# MAIN_BQ_INDUCTOR_REV.net
KiCad netlist of a schematic drawn in EAGLE
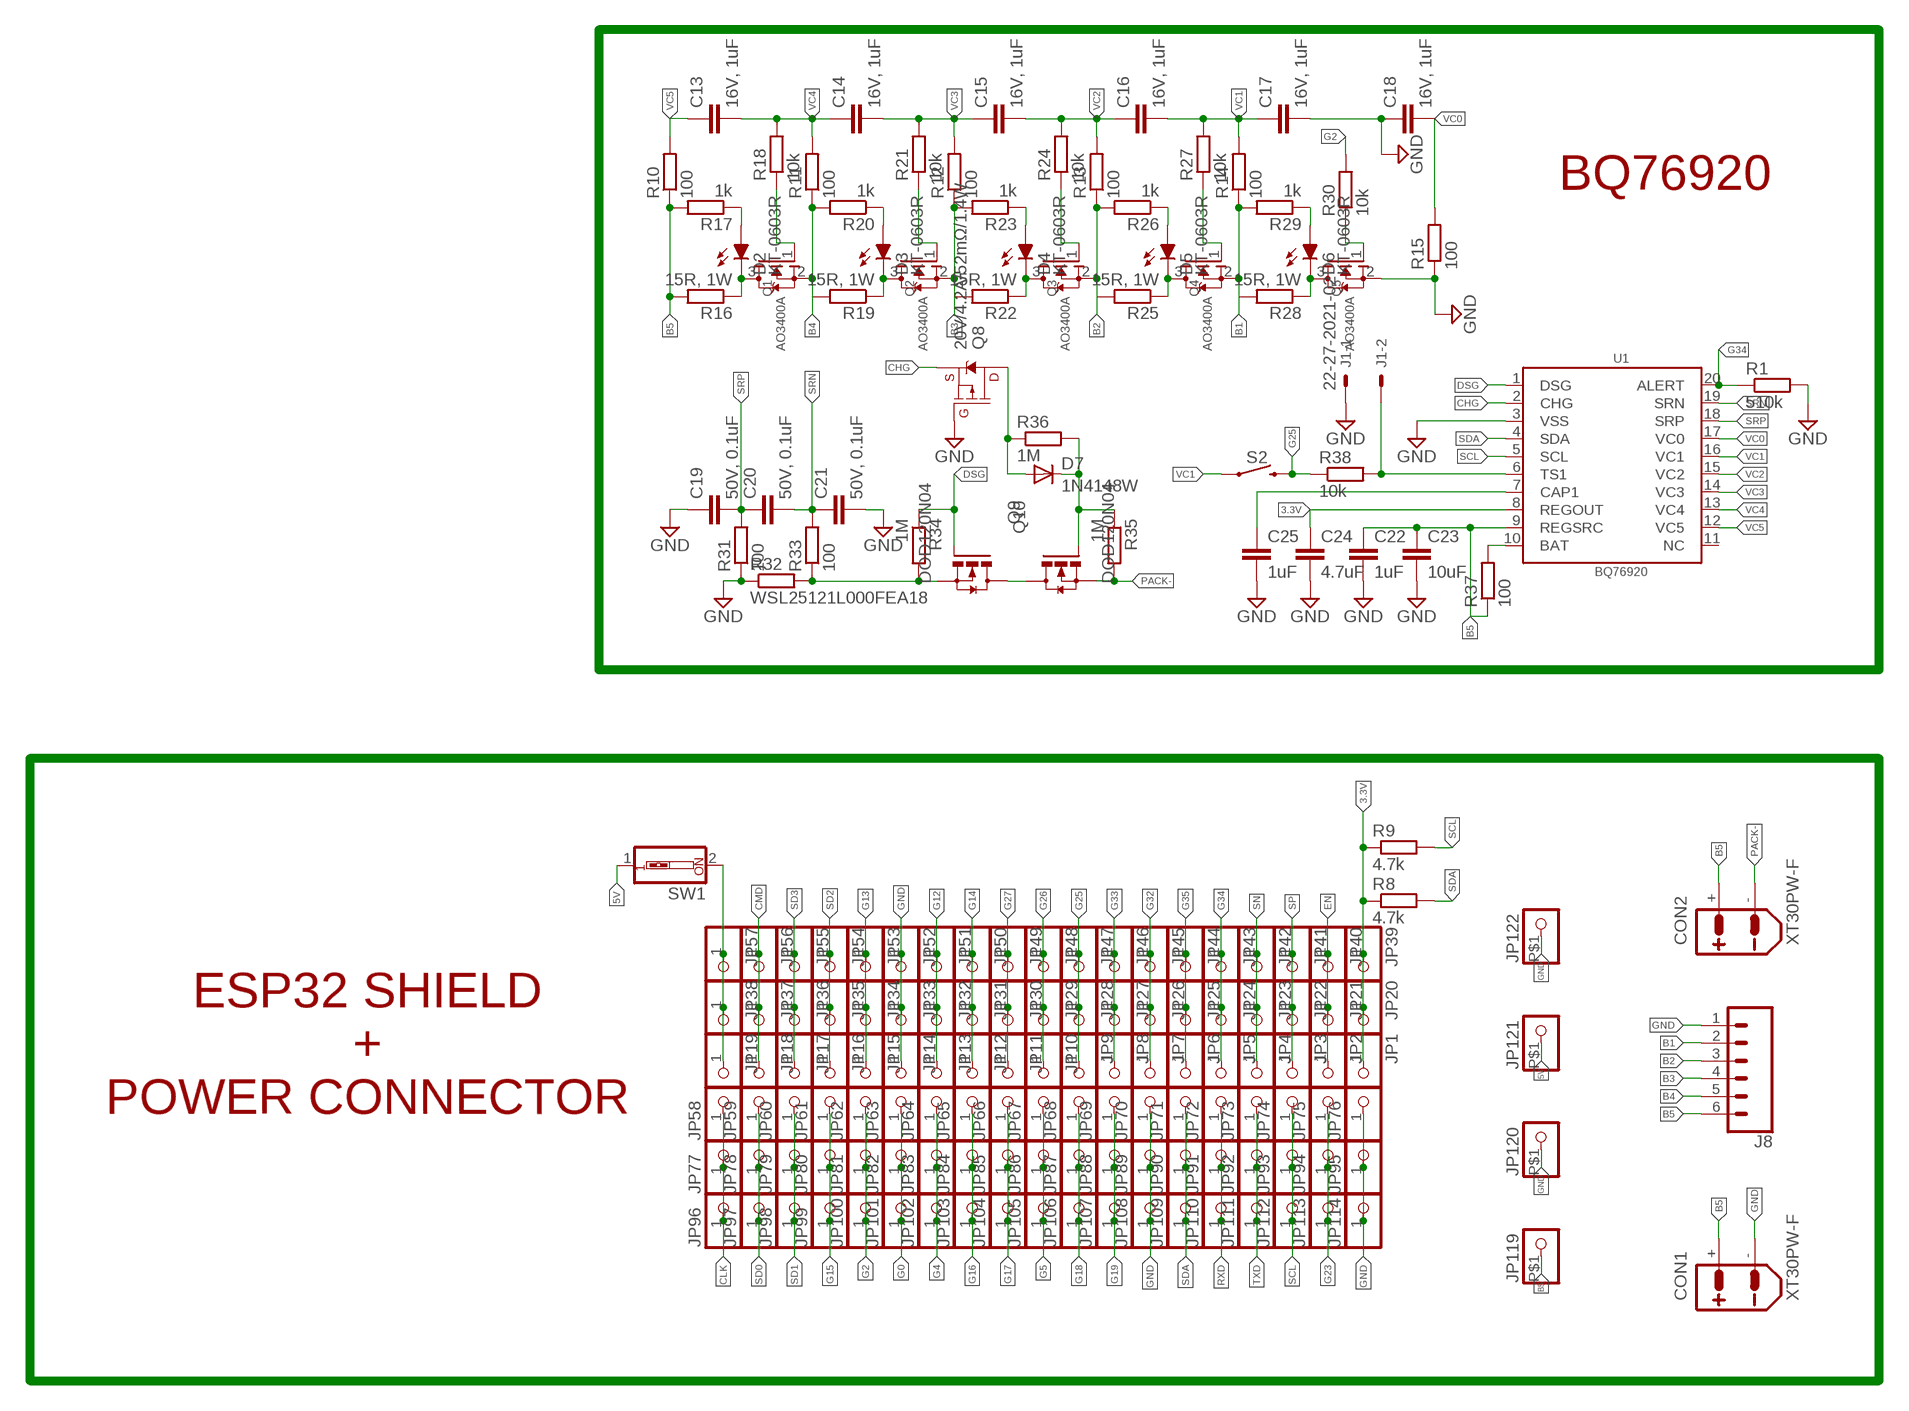
[diagram p0: schematic, sheet 1, part 1 of 2]
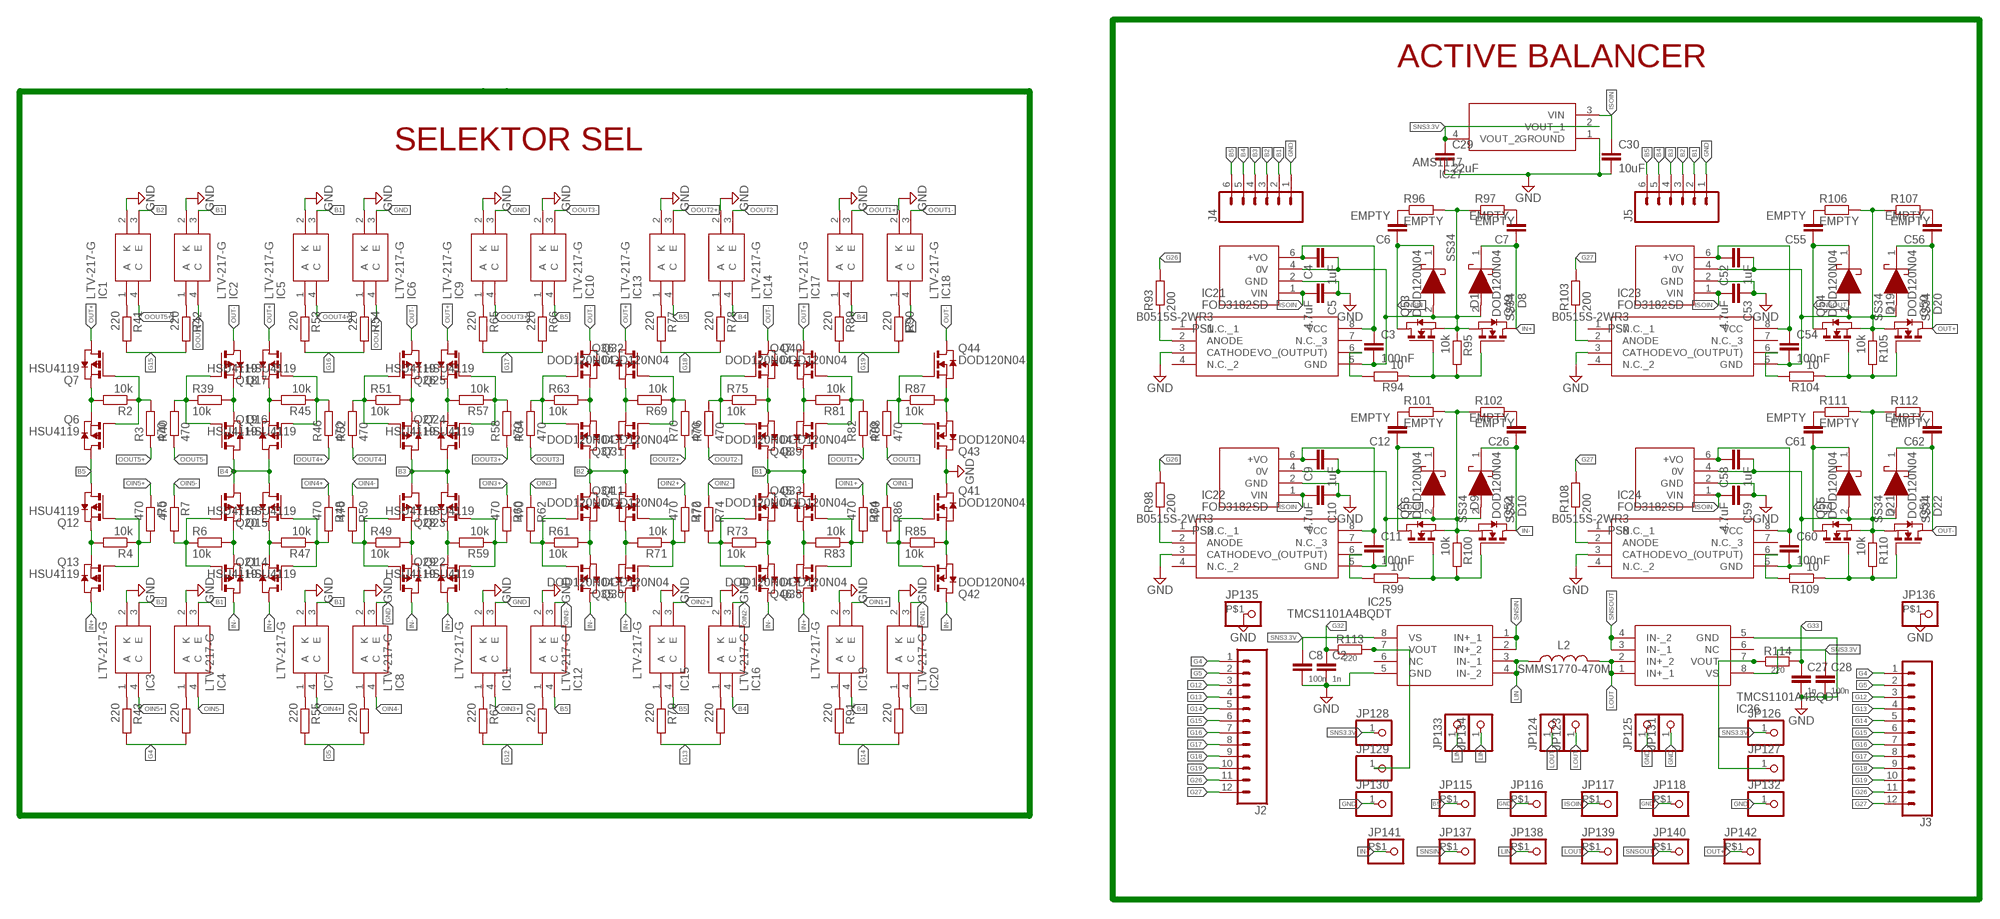
[diagram p1: schematic, sheet 1, part 2 of 2]

(export (version "E")
  (design (tool "Eeschema 10.0.6"))
  (components
    (comp (ref "C2")
      (value "1n")
      (footprint "eagle-import:C0805")
      (libsource (lib "eagle-import") (part "C-EUC0805"))
    )
    (comp (ref "C3")
      (value "100nF")
      (footprint "eagle-import:C0805")
      (libsource (lib "eagle-import") (part "rcl_334_C-EUC0805"))
    )
    (comp (ref "C4")
      (value "1uF")
      (footprint "eagle-import:C1206")
      (libsource (lib "eagle-import") (part "rcl_334_C-EUC1206"))
    )
    (comp (ref "C5")
      (value "4.7uF")
      (footprint "eagle-import:C1206")
      (libsource (lib "eagle-import") (part "rcl_334_C-EUC1206"))
    )
    (comp (ref "C6")
      (value "EMPTY")
      (footprint "eagle-import:C1206")
      (libsource (lib "eagle-import") (part "rcl_334_C-EUC1206"))
    )
    (comp (ref "C7")
      (value "EMPTY")
      (footprint "eagle-import:C1206")
      (libsource (lib "eagle-import") (part "rcl_334_C-EUC1206"))
    )
    (comp (ref "C8")
      (value "100n")
      (footprint "eagle-import:C0805")
      (libsource (lib "eagle-import") (part "C-EUC0805"))
    )
    (comp (ref "C9")
      (value "1uF")
      (footprint "eagle-import:C1206")
      (libsource (lib "eagle-import") (part "rcl_334_C-EUC1206"))
    )
    (comp (ref "C10")
      (value "4.7uF")
      (footprint "eagle-import:C1206")
      (libsource (lib "eagle-import") (part "rcl_334_C-EUC1206"))
    )
    (comp (ref "C11")
      (value "100nF")
      (footprint "eagle-import:C0805")
      (libsource (lib "eagle-import") (part "rcl_334_C-EUC0805"))
    )
    (comp (ref "C12")
      (value "EMPTY")
      (footprint "eagle-import:C1206")
      (libsource (lib "eagle-import") (part "rcl_334_C-EUC1206"))
    )
    (comp (ref "C13")
      (value "16V, 1uF")
      (footprint "eagle-import:C0805")
      (libsource (lib "eagle-import") (part "rcl_334_C-EUC0805"))
    )
    (comp (ref "C14")
      (value "16V, 1uF")
      (footprint "eagle-import:C0805")
      (libsource (lib "eagle-import") (part "rcl_334_C-EUC0805"))
    )
    (comp (ref "C15")
      (value "16V, 1uF")
      (footprint "eagle-import:C0805")
      (libsource (lib "eagle-import") (part "rcl_334_C-EUC0805"))
    )
    (comp (ref "C16")
      (value "16V, 1uF")
      (footprint "eagle-import:C0805")
      (libsource (lib "eagle-import") (part "rcl_334_C-EUC0805"))
    )
    (comp (ref "C17")
      (value "16V, 1uF")
      (footprint "eagle-import:C0805")
      (libsource (lib "eagle-import") (part "rcl_334_C-EUC0805"))
    )
    (comp (ref "C18")
      (value "16V, 1uF")
      (footprint "eagle-import:C0805")
      (libsource (lib "eagle-import") (part "rcl_334_C-EUC0805"))
    )
    (comp (ref "C19")
      (value "50V, 0.1uF")
      (footprint "eagle-import:C0603")
      (libsource (lib "eagle-import") (part "C-EUC0603"))
    )
    (comp (ref "C20")
      (value "50V, 0.1uF")
      (footprint "eagle-import:C0603")
      (libsource (lib "eagle-import") (part "C-EUC0603"))
    )
    (comp (ref "C21")
      (value "50V, 0.1uF")
      (footprint "eagle-import:C0603")
      (libsource (lib "eagle-import") (part "C-EUC0603"))
    )
    (comp (ref "C22")
      (value "1uF")
      (footprint "eagle-import:C0805")
      (libsource (lib "eagle-import") (part "rcl_334_C-EUC0805"))
    )
    (comp (ref "C23")
      (value "10uF")
      (footprint "eagle-import:C1206")
      (libsource (lib "eagle-import") (part "rcl_334_C-EUC1206"))
    )
    (comp (ref "C24")
      (value "4.7uF")
      (footprint "eagle-import:C0805")
      (libsource (lib "eagle-import") (part "rcl_334_C-EUC0805"))
    )
    (comp (ref "C25")
      (value "1uF")
      (footprint "eagle-import:C0805")
      (libsource (lib "eagle-import") (part "rcl_334_C-EUC0805"))
    )
    (comp (ref "C26")
      (value "EMPTY")
      (footprint "eagle-import:C1206")
      (libsource (lib "eagle-import") (part "rcl_334_C-EUC1206"))
    )
    (comp (ref "C27")
      (value "1n")
      (footprint "eagle-import:C0805")
      (libsource (lib "eagle-import") (part "C-EUC0805"))
    )
    (comp (ref "C28")
      (value "100n")
      (footprint "eagle-import:C0805")
      (libsource (lib "eagle-import") (part "C-EUC0805"))
    )
    (comp (ref "C29")
      (value "22uF")
      (footprint "eagle-import:C0805")
      (libsource (lib "eagle-import") (part "rcl_334_C-EUC0805"))
    )
    (comp (ref "C30")
      (value "10uF")
      (footprint "eagle-import:C0805")
      (libsource (lib "eagle-import") (part "rcl_334_C-EUC0805"))
    )
    (comp (ref "C52")
      (value "1uF")
      (footprint "eagle-import:C1206")
      (libsource (lib "eagle-import") (part "rcl_334_C-EUC1206"))
    )
    (comp (ref "C53")
      (value "4.7uF")
      (footprint "eagle-import:C1206")
      (libsource (lib "eagle-import") (part "rcl_334_C-EUC1206"))
    )
    (comp (ref "C54")
      (value "100nF")
      (footprint "eagle-import:C0805")
      (libsource (lib "eagle-import") (part "rcl_334_C-EUC0805"))
    )
    (comp (ref "C55")
      (value "EMPTY")
      (footprint "eagle-import:C1206")
      (libsource (lib "eagle-import") (part "rcl_334_C-EUC1206"))
    )
    (comp (ref "C56")
      (value "EMPTY")
      (footprint "eagle-import:C1206")
      (libsource (lib "eagle-import") (part "rcl_334_C-EUC1206"))
    )
    (comp (ref "C58")
      (value "1uF")
      (footprint "eagle-import:C1206")
      (libsource (lib "eagle-import") (part "rcl_334_C-EUC1206"))
    )
    (comp (ref "C59")
      (value "4.7uF")
      (footprint "eagle-import:C1206")
      (libsource (lib "eagle-import") (part "rcl_334_C-EUC1206"))
    )
    (comp (ref "C60")
      (value "100nF")
      (footprint "eagle-import:C0805")
      (libsource (lib "eagle-import") (part "rcl_334_C-EUC0805"))
    )
    (comp (ref "C61")
      (value "EMPTY")
      (footprint "eagle-import:C1206")
      (libsource (lib "eagle-import") (part "rcl_334_C-EUC1206"))
    )
    (comp (ref "C62")
      (value "EMPTY")
      (footprint "eagle-import:C1206")
      (libsource (lib "eagle-import") (part "rcl_334_C-EUC1206"))
    )
    (comp (ref "CON1")
      (value "XT30PW-F")
      (footprint "eagle-import:XT30PW-F")
      (libsource (lib "eagle-import") (part "XT30PW-F"))
    )
    (comp (ref "CON2")
      (value "XT30PW-F")
      (footprint "eagle-import:XT30PW-F")
      (libsource (lib "eagle-import") (part "XT30PW-F"))
    )
    (comp (ref "D1")
      (value "SS34")
      (footprint "eagle-import:DIOM6959X262N")
      (libsource (lib "eagle-import") (part "SS34"))
    )
    (comp (ref "D2")
      (value "KT-0603R")
      (footprint "eagle-import:LED_CHIP-LED0603MP")
      (libsource (lib "eagle-import") (part "LED_LEDCHIP-LED0603MP"))
    )
    (comp (ref "D3")
      (value "KT-0603R")
      (footprint "eagle-import:LED_CHIP-LED0603MP")
      (libsource (lib "eagle-import") (part "LED_LEDCHIP-LED0603MP"))
    )
    (comp (ref "D4")
      (value "KT-0603R")
      (footprint "eagle-import:LED_CHIP-LED0603MP")
      (libsource (lib "eagle-import") (part "LED_LEDCHIP-LED0603MP"))
    )
    (comp (ref "D5")
      (value "KT-0603R")
      (footprint "eagle-import:LED_CHIP-LED0603MP")
      (libsource (lib "eagle-import") (part "LED_LEDCHIP-LED0603MP"))
    )
    (comp (ref "D6")
      (value "KT-0603R")
      (footprint "eagle-import:LED_CHIP-LED0603MP")
      (libsource (lib "eagle-import") (part "LED_LEDCHIP-LED0603MP"))
    )
    (comp (ref "D7")
      (value "1N4148W")
      (footprint "eagle-import:SOD-123")
      (libsource (lib "eagle-import") (part "DIODESOD-123"))
    )
    (comp (ref "D8")
      (value "SS34")
      (footprint "eagle-import:DIOM6959X262N")
      (libsource (lib "eagle-import") (part "SS34"))
    )
    (comp (ref "D9")
      (value "SS34")
      (footprint "eagle-import:DIOM6959X262N")
      (libsource (lib "eagle-import") (part "SS34"))
    )
    (comp (ref "D10")
      (value "SS34")
      (footprint "eagle-import:DIOM6959X262N")
      (libsource (lib "eagle-import") (part "SS34"))
    )
    (comp (ref "D19")
      (value "SS34")
      (footprint "eagle-import:DIOM6959X262N")
      (libsource (lib "eagle-import") (part "SS34"))
    )
    (comp (ref "D20")
      (value "SS34")
      (footprint "eagle-import:DIOM6959X262N")
      (libsource (lib "eagle-import") (part "SS34"))
    )
    (comp (ref "D21")
      (value "SS34")
      (footprint "eagle-import:DIOM6959X262N")
      (libsource (lib "eagle-import") (part "SS34"))
    )
    (comp (ref "D22")
      (value "SS34")
      (footprint "eagle-import:DIOM6959X262N")
      (libsource (lib "eagle-import") (part "SS34"))
    )
    (comp (ref "IC1")
      (value "LTV-217-G")
      (footprint "eagle-import:LTV217G")
      (fields (field (name "MOUSER_PART_NUMBER") "859-LTV217G"))
      (libsource (lib "eagle-import") (part "LTV-217-G"))
    )
    (comp (ref "IC2")
      (value "LTV-217-G")
      (footprint "eagle-import:LTV217G")
      (fields (field (name "MOUSER_PART_NUMBER") "859-LTV217G"))
      (libsource (lib "eagle-import") (part "LTV-217-G"))
    )
    (comp (ref "IC3")
      (value "LTV-217-G")
      (footprint "eagle-import:LTV217G")
      (fields (field (name "MOUSER_PART_NUMBER") "859-LTV217G"))
      (libsource (lib "eagle-import") (part "LTV-217-G"))
    )
    (comp (ref "IC4")
      (value "LTV-217-G")
      (footprint "eagle-import:LTV217G")
      (fields (field (name "MOUSER_PART_NUMBER") "859-LTV217G"))
      (libsource (lib "eagle-import") (part "LTV-217-G"))
    )
    (comp (ref "IC5")
      (value "LTV-217-G")
      (footprint "eagle-import:LTV217G")
      (fields (field (name "MOUSER_PART_NUMBER") "859-LTV217G"))
      (libsource (lib "eagle-import") (part "LTV-217-G"))
    )
    (comp (ref "IC6")
      (value "LTV-217-G")
      (footprint "eagle-import:LTV217G")
      (fields (field (name "MOUSER_PART_NUMBER") "859-LTV217G"))
      (libsource (lib "eagle-import") (part "LTV-217-G"))
    )
    (comp (ref "IC7")
      (value "LTV-217-G")
      (footprint "eagle-import:LTV217G")
      (fields (field (name "MOUSER_PART_NUMBER") "859-LTV217G"))
      (libsource (lib "eagle-import") (part "LTV-217-G"))
    )
    (comp (ref "IC8")
      (value "LTV-217-G")
      (footprint "eagle-import:LTV217G")
      (fields (field (name "MOUSER_PART_NUMBER") "859-LTV217G"))
      (libsource (lib "eagle-import") (part "LTV-217-G"))
    )
    (comp (ref "IC9")
      (value "LTV-217-G")
      (footprint "eagle-import:LTV217G")
      (fields (field (name "MOUSER_PART_NUMBER") "859-LTV217G"))
      (libsource (lib "eagle-import") (part "LTV-217-G"))
    )
    (comp (ref "IC10")
      (value "LTV-217-G")
      (footprint "eagle-import:LTV217G")
      (fields (field (name "MOUSER_PART_NUMBER") "859-LTV217G"))
      (libsource (lib "eagle-import") (part "LTV-217-G"))
    )
    (comp (ref "IC11")
      (value "LTV-217-G")
      (footprint "eagle-import:LTV217G")
      (fields (field (name "MOUSER_PART_NUMBER") "859-LTV217G"))
      (libsource (lib "eagle-import") (part "LTV-217-G"))
    )
    (comp (ref "IC12")
      (value "LTV-217-G")
      (footprint "eagle-import:LTV217G")
      (fields (field (name "MOUSER_PART_NUMBER") "859-LTV217G"))
      (libsource (lib "eagle-import") (part "LTV-217-G"))
    )
    (comp (ref "IC13")
      (value "LTV-217-G")
      (footprint "eagle-import:LTV217G")
      (fields (field (name "MOUSER_PART_NUMBER") "859-LTV217G"))
      (libsource (lib "eagle-import") (part "LTV-217-G"))
    )
    (comp (ref "IC14")
      (value "LTV-217-G")
      (footprint "eagle-import:LTV217G")
      (fields (field (name "MOUSER_PART_NUMBER") "859-LTV217G"))
      (libsource (lib "eagle-import") (part "LTV-217-G"))
    )
    (comp (ref "IC15")
      (value "LTV-217-G")
      (footprint "eagle-import:LTV217G")
      (fields (field (name "MOUSER_PART_NUMBER") "859-LTV217G"))
      (libsource (lib "eagle-import") (part "LTV-217-G"))
    )
    (comp (ref "IC16")
      (value "LTV-217-G")
      (footprint "eagle-import:LTV217G")
      (fields (field (name "MOUSER_PART_NUMBER") "859-LTV217G"))
      (libsource (lib "eagle-import") (part "LTV-217-G"))
    )
    (comp (ref "IC17")
      (value "LTV-217-G")
      (footprint "eagle-import:LTV217G")
      (fields (field (name "MOUSER_PART_NUMBER") "859-LTV217G"))
      (libsource (lib "eagle-import") (part "LTV-217-G"))
    )
    (comp (ref "IC18")
      (value "LTV-217-G")
      (footprint "eagle-import:LTV217G")
      (fields (field (name "MOUSER_PART_NUMBER") "859-LTV217G"))
      (libsource (lib "eagle-import") (part "LTV-217-G"))
    )
    (comp (ref "IC19")
      (value "LTV-217-G")
      (footprint "eagle-import:LTV217G")
      (fields (field (name "MOUSER_PART_NUMBER") "859-LTV217G"))
      (libsource (lib "eagle-import") (part "LTV-217-G"))
    )
    (comp (ref "IC20")
      (value "LTV-217-G")
      (footprint "eagle-import:LTV217G")
      (fields (field (name "MOUSER_PART_NUMBER") "859-LTV217G"))
      (libsource (lib "eagle-import") (part "LTV-217-G"))
    )
    (comp (ref "IC21")
      (value "FOD3182SD")
      (footprint "eagle-import:SOP254P1000X400-8N")
      (fields (field (name "ARROW_PART_NUMBER") "TLP350(TP5,F)"))
      (libsource (lib "eagle-import") (part "TLP350_TP5,F_"))
    )
    (comp (ref "IC22")
      (value "FOD3182SD")
      (footprint "eagle-import:SOP254P1000X400-8N")
      (fields (field (name "ARROW_PART_NUMBER") "TLP350(TP5,F)"))
      (libsource (lib "eagle-import") (part "TLP350_TP5,F_"))
    )
    (comp (ref "IC23")
      (value "FOD3182SD")
      (footprint "eagle-import:SOP254P1000X400-8N")
      (fields (field (name "ARROW_PART_NUMBER") "TLP350(TP5,F)"))
      (libsource (lib "eagle-import") (part "TLP350_TP5,F_"))
    )
    (comp (ref "IC24")
      (value "FOD3182SD")
      (footprint "eagle-import:SOP254P1000X400-8N")
      (fields (field (name "ARROW_PART_NUMBER") "TLP350(TP5,F)"))
      (libsource (lib "eagle-import") (part "TLP350_TP5,F_"))
    )
    (comp (ref "IC25")
      (value "TMCS1101A4BQDT")
      (footprint "eagle-import:SOIC127P600X175-8N")
      (fields (field (name "MOUSER_PART_NUMBER") "595-TMCS1101A4BQDT"))
      (libsource (lib "eagle-import") (part "TMCS1101A4BQDT"))
    )
    (comp (ref "IC26")
      (value "TMCS1101A4BQDT")
      (footprint "eagle-import:SOIC127P600X175-8N")
      (fields (field (name "MOUSER_PART_NUMBER") "595-TMCS1101A4BQDT"))
      (libsource (lib "eagle-import") (part "TMCS1101A4BQDT"))
    )
    (comp (ref "IC27")
      (value "AMS1117")
      (footprint "eagle-import:SOT229P700X180-4N")
      (libsource (lib "eagle-import") (part "AMS1117"))
    )
    (comp (ref "J1")
      (value "22-27-2021-02")
      (footprint "eagle-import:6410-02")
      (fields (field (name "MF") "MOLEX"))
      (libsource (lib "eagle-import") (part "22-?-0227-2021"))
    )
    (comp (ref "J2")
      (value "CONN_12")
      (footprint "eagle-import:1X12")
      (libsource (lib "eagle-import") (part "CONN_12"))
    )
    (comp (ref "J3")
      (value "CONN_12")
      (footprint "eagle-import:1X12")
      (libsource (lib "eagle-import") (part "CONN_12"))
    )
    (comp (ref "J4")
      (value "CONN_06LONGPADS")
      (footprint "eagle-import:1X06_LONGPADS")
      (libsource (lib "eagle-import") (part "CONN_06LONGPADS"))
    )
    (comp (ref "J5")
      (value "CONN_06LONGPADS")
      (footprint "eagle-import:1X06_LONGPADS")
      (libsource (lib "eagle-import") (part "CONN_06LONGPADS"))
    )
    (comp (ref "J8")
      (value "CONN_06LONGPADS")
      (footprint "eagle-import:1X06_LONGPADS")
      (libsource (lib "eagle-import") (part "CONN_06LONGPADS"))
    )
    (comp (ref "JP1")
      (value "PINHD-1X1")
      (footprint "eagle-import:1X01")
      (libsource (lib "eagle-import") (part "PINHD-1X1"))
    )
    (comp (ref "JP2")
      (value "PINHD-1X1")
      (footprint "eagle-import:1X01")
      (libsource (lib "eagle-import") (part "PINHD-1X1"))
    )
    (comp (ref "JP3")
      (value "PINHD-1X1")
      (footprint "eagle-import:1X01")
      (libsource (lib "eagle-import") (part "PINHD-1X1"))
    )
    (comp (ref "JP4")
      (value "PINHD-1X1")
      (footprint "eagle-import:1X01")
      (libsource (lib "eagle-import") (part "PINHD-1X1"))
    )
    (comp (ref "JP5")
      (value "PINHD-1X1")
      (footprint "eagle-import:1X01")
      (libsource (lib "eagle-import") (part "PINHD-1X1"))
    )
    (comp (ref "JP6")
      (value "PINHD-1X1")
      (footprint "eagle-import:1X01")
      (libsource (lib "eagle-import") (part "PINHD-1X1"))
    )
    (comp (ref "JP7")
      (value "PINHD-1X1")
      (footprint "eagle-import:1X01")
      (libsource (lib "eagle-import") (part "PINHD-1X1"))
    )
    (comp (ref "JP8")
      (value "PINHD-1X1")
      (footprint "eagle-import:1X01")
      (libsource (lib "eagle-import") (part "PINHD-1X1"))
    )
    (comp (ref "JP9")
      (value "PINHD-1X1")
      (footprint "eagle-import:1X01")
      (libsource (lib "eagle-import") (part "PINHD-1X1"))
    )
    (comp (ref "JP10")
      (value "PINHD-1X1")
      (footprint "eagle-import:1X01")
      (libsource (lib "eagle-import") (part "PINHD-1X1"))
    )
    (comp (ref "JP11")
      (value "PINHD-1X1")
      (footprint "eagle-import:1X01")
      (libsource (lib "eagle-import") (part "PINHD-1X1"))
    )
    (comp (ref "JP12")
      (value "PINHD-1X1")
      (footprint "eagle-import:1X01")
      (libsource (lib "eagle-import") (part "PINHD-1X1"))
    )
    (comp (ref "JP13")
      (value "PINHD-1X1")
      (footprint "eagle-import:1X01")
      (libsource (lib "eagle-import") (part "PINHD-1X1"))
    )
    (comp (ref "JP14")
      (value "PINHD-1X1")
      (footprint "eagle-import:1X01")
      (libsource (lib "eagle-import") (part "PINHD-1X1"))
    )
    (comp (ref "JP15")
      (value "PINHD-1X1")
      (footprint "eagle-import:1X01")
      (libsource (lib "eagle-import") (part "PINHD-1X1"))
    )
    (comp (ref "JP16")
      (value "PINHD-1X1")
      (footprint "eagle-import:1X01")
      (libsource (lib "eagle-import") (part "PINHD-1X1"))
    )
    (comp (ref "JP17")
      (value "PINHD-1X1")
      (footprint "eagle-import:1X01")
      (libsource (lib "eagle-import") (part "PINHD-1X1"))
    )
    (comp (ref "JP18")
      (value "PINHD-1X1")
      (footprint "eagle-import:1X01")
      (libsource (lib "eagle-import") (part "PINHD-1X1"))
    )
    (comp (ref "JP19")
      (value "PINHD-1X1")
      (footprint "eagle-import:1X01")
      (libsource (lib "eagle-import") (part "PINHD-1X1"))
    )
    (comp (ref "JP20")
      (value "PINHD-1X1")
      (footprint "eagle-import:1X01")
      (libsource (lib "eagle-import") (part "PINHD-1X1"))
    )
    (comp (ref "JP21")
      (value "PINHD-1X1")
      (footprint "eagle-import:1X01")
      (libsource (lib "eagle-import") (part "PINHD-1X1"))
    )
    (comp (ref "JP22")
      (value "PINHD-1X1")
      (footprint "eagle-import:1X01")
      (libsource (lib "eagle-import") (part "PINHD-1X1"))
    )
    (comp (ref "JP23")
      (value "PINHD-1X1")
      (footprint "eagle-import:1X01")
      (libsource (lib "eagle-import") (part "PINHD-1X1"))
    )
    (comp (ref "JP24")
      (value "PINHD-1X1")
      (footprint "eagle-import:1X01")
      (libsource (lib "eagle-import") (part "PINHD-1X1"))
    )
    (comp (ref "JP25")
      (value "PINHD-1X1")
      (footprint "eagle-import:1X01")
      (libsource (lib "eagle-import") (part "PINHD-1X1"))
    )
    (comp (ref "JP26")
      (value "PINHD-1X1")
      (footprint "eagle-import:1X01")
      (libsource (lib "eagle-import") (part "PINHD-1X1"))
    )
    (comp (ref "JP27")
      (value "PINHD-1X1")
      (footprint "eagle-import:1X01")
      (libsource (lib "eagle-import") (part "PINHD-1X1"))
    )
    (comp (ref "JP28")
      (value "PINHD-1X1")
      (footprint "eagle-import:1X01")
      (libsource (lib "eagle-import") (part "PINHD-1X1"))
    )
    (comp (ref "JP29")
      (value "PINHD-1X1")
      (footprint "eagle-import:1X01")
      (libsource (lib "eagle-import") (part "PINHD-1X1"))
    )
    (comp (ref "JP30")
      (value "PINHD-1X1")
      (footprint "eagle-import:1X01")
      (libsource (lib "eagle-import") (part "PINHD-1X1"))
    )
    (comp (ref "JP31")
      (value "PINHD-1X1")
      (footprint "eagle-import:1X01")
      (libsource (lib "eagle-import") (part "PINHD-1X1"))
    )
    (comp (ref "JP32")
      (value "PINHD-1X1")
      (footprint "eagle-import:1X01")
      (libsource (lib "eagle-import") (part "PINHD-1X1"))
    )
    (comp (ref "JP33")
      (value "PINHD-1X1")
      (footprint "eagle-import:1X01")
      (libsource (lib "eagle-import") (part "PINHD-1X1"))
    )
    (comp (ref "JP34")
      (value "PINHD-1X1")
      (footprint "eagle-import:1X01")
      (libsource (lib "eagle-import") (part "PINHD-1X1"))
    )
    (comp (ref "JP35")
      (value "PINHD-1X1")
      (footprint "eagle-import:1X01")
      (libsource (lib "eagle-import") (part "PINHD-1X1"))
    )
    (comp (ref "JP36")
      (value "PINHD-1X1")
      (footprint "eagle-import:1X01")
      (libsource (lib "eagle-import") (part "PINHD-1X1"))
    )
    (comp (ref "JP37")
      (value "PINHD-1X1")
      (footprint "eagle-import:1X01")
      (libsource (lib "eagle-import") (part "PINHD-1X1"))
    )
    (comp (ref "JP38")
      (value "PINHD-1X1")
      (footprint "eagle-import:1X01")
      (libsource (lib "eagle-import") (part "PINHD-1X1"))
    )
    (comp (ref "JP39")
      (value "PINHD-1X1")
      (footprint "eagle-import:1X01")
      (libsource (lib "eagle-import") (part "PINHD-1X1"))
    )
    (comp (ref "JP40")
      (value "PINHD-1X1")
      (footprint "eagle-import:1X01")
      (libsource (lib "eagle-import") (part "PINHD-1X1"))
    )
    (comp (ref "JP41")
      (value "PINHD-1X1")
      (footprint "eagle-import:1X01")
      (libsource (lib "eagle-import") (part "PINHD-1X1"))
    )
    (comp (ref "JP42")
      (value "PINHD-1X1")
      (footprint "eagle-import:1X01")
      (libsource (lib "eagle-import") (part "PINHD-1X1"))
    )
    (comp (ref "JP43")
      (value "PINHD-1X1")
      (footprint "eagle-import:1X01")
      (libsource (lib "eagle-import") (part "PINHD-1X1"))
    )
    (comp (ref "JP44")
      (value "PINHD-1X1")
      (footprint "eagle-import:1X01")
      (libsource (lib "eagle-import") (part "PINHD-1X1"))
    )
    (comp (ref "JP45")
      (value "PINHD-1X1")
      (footprint "eagle-import:1X01")
      (libsource (lib "eagle-import") (part "PINHD-1X1"))
    )
    (comp (ref "JP46")
      (value "PINHD-1X1")
      (footprint "eagle-import:1X01")
      (libsource (lib "eagle-import") (part "PINHD-1X1"))
    )
    (comp (ref "JP47")
      (value "PINHD-1X1")
      (footprint "eagle-import:1X01")
      (libsource (lib "eagle-import") (part "PINHD-1X1"))
    )
    (comp (ref "JP48")
      (value "PINHD-1X1")
      (footprint "eagle-import:1X01")
      (libsource (lib "eagle-import") (part "PINHD-1X1"))
    )
    (comp (ref "JP49")
      (value "PINHD-1X1")
      (footprint "eagle-import:1X01")
      (libsource (lib "eagle-import") (part "PINHD-1X1"))
    )
    (comp (ref "JP50")
      (value "PINHD-1X1")
      (footprint "eagle-import:1X01")
      (libsource (lib "eagle-import") (part "PINHD-1X1"))
    )
    (comp (ref "JP51")
      (value "PINHD-1X1")
      (footprint "eagle-import:1X01")
      (libsource (lib "eagle-import") (part "PINHD-1X1"))
    )
    (comp (ref "JP52")
      (value "PINHD-1X1")
      (footprint "eagle-import:1X01")
      (libsource (lib "eagle-import") (part "PINHD-1X1"))
    )
    (comp (ref "JP53")
      (value "PINHD-1X1")
      (footprint "eagle-import:1X01")
      (libsource (lib "eagle-import") (part "PINHD-1X1"))
    )
    (comp (ref "JP54")
      (value "PINHD-1X1")
      (footprint "eagle-import:1X01")
      (libsource (lib "eagle-import") (part "PINHD-1X1"))
    )
    (comp (ref "JP55")
      (value "PINHD-1X1")
      (footprint "eagle-import:1X01")
      (libsource (lib "eagle-import") (part "PINHD-1X1"))
    )
    (comp (ref "JP56")
      (value "PINHD-1X1")
      (footprint "eagle-import:1X01")
      (libsource (lib "eagle-import") (part "PINHD-1X1"))
    )
    (comp (ref "JP57")
      (value "PINHD-1X1")
      (footprint "eagle-import:1X01")
      (libsource (lib "eagle-import") (part "PINHD-1X1"))
    )
    (comp (ref "JP58")
      (value "PINHD-1X1")
      (footprint "eagle-import:1X01")
      (libsource (lib "eagle-import") (part "PINHD-1X1"))
    )
    (comp (ref "JP59")
      (value "PINHD-1X1")
      (footprint "eagle-import:1X01")
      (libsource (lib "eagle-import") (part "PINHD-1X1"))
    )
    (comp (ref "JP60")
      (value "PINHD-1X1")
      (footprint "eagle-import:1X01")
      (libsource (lib "eagle-import") (part "PINHD-1X1"))
    )
    (comp (ref "JP61")
      (value "PINHD-1X1")
      (footprint "eagle-import:1X01")
      (libsource (lib "eagle-import") (part "PINHD-1X1"))
    )
    (comp (ref "JP62")
      (value "PINHD-1X1")
      (footprint "eagle-import:1X01")
      (libsource (lib "eagle-import") (part "PINHD-1X1"))
    )
    (comp (ref "JP63")
      (value "PINHD-1X1")
      (footprint "eagle-import:1X01")
      (libsource (lib "eagle-import") (part "PINHD-1X1"))
    )
    (comp (ref "JP64")
      (value "PINHD-1X1")
      (footprint "eagle-import:1X01")
      (libsource (lib "eagle-import") (part "PINHD-1X1"))
    )
    (comp (ref "JP65")
      (value "PINHD-1X1")
      (footprint "eagle-import:1X01")
      (libsource (lib "eagle-import") (part "PINHD-1X1"))
    )
    (comp (ref "JP66")
      (value "PINHD-1X1")
      (footprint "eagle-import:1X01")
      (libsource (lib "eagle-import") (part "PINHD-1X1"))
    )
    (comp (ref "JP67")
      (value "PINHD-1X1")
      (footprint "eagle-import:1X01")
      (libsource (lib "eagle-import") (part "PINHD-1X1"))
    )
    (comp (ref "JP68")
      (value "PINHD-1X1")
      (footprint "eagle-import:1X01")
      (libsource (lib "eagle-import") (part "PINHD-1X1"))
    )
    (comp (ref "JP69")
      (value "PINHD-1X1")
      (footprint "eagle-import:1X01")
      (libsource (lib "eagle-import") (part "PINHD-1X1"))
    )
    (comp (ref "JP70")
      (value "PINHD-1X1")
      (footprint "eagle-import:1X01")
      (libsource (lib "eagle-import") (part "PINHD-1X1"))
    )
    (comp (ref "JP71")
      (value "PINHD-1X1")
      (footprint "eagle-import:1X01")
      (libsource (lib "eagle-import") (part "PINHD-1X1"))
    )
    (comp (ref "JP72")
      (value "PINHD-1X1")
      (footprint "eagle-import:1X01")
      (libsource (lib "eagle-import") (part "PINHD-1X1"))
    )
    (comp (ref "JP73")
      (value "PINHD-1X1")
      (footprint "eagle-import:1X01")
      (libsource (lib "eagle-import") (part "PINHD-1X1"))
    )
    (comp (ref "JP74")
      (value "PINHD-1X1")
      (footprint "eagle-import:1X01")
      (libsource (lib "eagle-import") (part "PINHD-1X1"))
    )
    (comp (ref "JP75")
      (value "PINHD-1X1")
      (footprint "eagle-import:1X01")
      (libsource (lib "eagle-import") (part "PINHD-1X1"))
    )
    (comp (ref "JP76")
      (value "PINHD-1X1")
      (footprint "eagle-import:1X01")
      (libsource (lib "eagle-import") (part "PINHD-1X1"))
    )
    (comp (ref "JP77")
      (value "PINHD-1X1")
      (footprint "eagle-import:1X01")
      (libsource (lib "eagle-import") (part "PINHD-1X1"))
    )
    (comp (ref "JP78")
      (value "PINHD-1X1")
      (footprint "eagle-import:1X01")
      (libsource (lib "eagle-import") (part "PINHD-1X1"))
    )
    (comp (ref "JP79")
      (value "PINHD-1X1")
      (footprint "eagle-import:1X01")
      (libsource (lib "eagle-import") (part "PINHD-1X1"))
    )
    (comp (ref "JP80")
      (value "PINHD-1X1")
      (footprint "eagle-import:1X01")
      (libsource (lib "eagle-import") (part "PINHD-1X1"))
    )
    (comp (ref "JP81")
      (value "PINHD-1X1")
      (footprint "eagle-import:1X01")
      (libsource (lib "eagle-import") (part "PINHD-1X1"))
    )
    (comp (ref "JP82")
      (value "PINHD-1X1")
      (footprint "eagle-import:1X01")
      (libsource (lib "eagle-import") (part "PINHD-1X1"))
    )
    (comp (ref "JP83")
      (value "PINHD-1X1")
      (footprint "eagle-import:1X01")
      (libsource (lib "eagle-import") (part "PINHD-1X1"))
    )
    (comp (ref "JP84")
      (value "PINHD-1X1")
      (footprint "eagle-import:1X01")
      (libsource (lib "eagle-import") (part "PINHD-1X1"))
    )
    (comp (ref "JP85")
      (value "PINHD-1X1")
      (footprint "eagle-import:1X01")
      (libsource (lib "eagle-import") (part "PINHD-1X1"))
    )
    (comp (ref "JP86")
      (value "PINHD-1X1")
      (footprint "eagle-import:1X01")
      (libsource (lib "eagle-import") (part "PINHD-1X1"))
    )
    (comp (ref "JP87")
      (value "PINHD-1X1")
      (footprint "eagle-import:1X01")
      (libsource (lib "eagle-import") (part "PINHD-1X1"))
    )
    (comp (ref "JP88")
      (value "PINHD-1X1")
      (footprint "eagle-import:1X01")
      (libsource (lib "eagle-import") (part "PINHD-1X1"))
    )
    (comp (ref "JP89")
      (value "PINHD-1X1")
      (footprint "eagle-import:1X01")
      (libsource (lib "eagle-import") (part "PINHD-1X1"))
    )
    (comp (ref "JP90")
      (value "PINHD-1X1")
      (footprint "eagle-import:1X01")
      (libsource (lib "eagle-import") (part "PINHD-1X1"))
    )
    (comp (ref "JP91")
      (value "PINHD-1X1")
      (footprint "eagle-import:1X01")
      (libsource (lib "eagle-import") (part "PINHD-1X1"))
    )
    (comp (ref "JP92")
      (value "PINHD-1X1")
      (footprint "eagle-import:1X01")
      (libsource (lib "eagle-import") (part "PINHD-1X1"))
    )
    (comp (ref "JP93")
      (value "PINHD-1X1")
      (footprint "eagle-import:1X01")
      (libsource (lib "eagle-import") (part "PINHD-1X1"))
    )
    (comp (ref "JP94")
      (value "PINHD-1X1")
      (footprint "eagle-import:1X01")
      (libsource (lib "eagle-import") (part "PINHD-1X1"))
    )
    (comp (ref "JP95")
      (value "PINHD-1X1")
      (footprint "eagle-import:1X01")
      (libsource (lib "eagle-import") (part "PINHD-1X1"))
    )
    (comp (ref "JP96")
      (value "PINHD-1X1")
      (footprint "eagle-import:1X01")
      (libsource (lib "eagle-import") (part "PINHD-1X1"))
    )
    (comp (ref "JP97")
      (value "PINHD-1X1")
      (footprint "eagle-import:1X01")
      (libsource (lib "eagle-import") (part "PINHD-1X1"))
    )
    (comp (ref "JP98")
      (value "PINHD-1X1")
      (footprint "eagle-import:1X01")
      (libsource (lib "eagle-import") (part "PINHD-1X1"))
    )
    (comp (ref "JP99")
      (value "PINHD-1X1")
      (footprint "eagle-import:1X01")
      (libsource (lib "eagle-import") (part "PINHD-1X1"))
    )
    (comp (ref "JP100")
      (value "PINHD-1X1")
      (footprint "eagle-import:1X01")
      (libsource (lib "eagle-import") (part "PINHD-1X1"))
    )
    (comp (ref "JP101")
      (value "PINHD-1X1")
      (footprint "eagle-import:1X01")
      (libsource (lib "eagle-import") (part "PINHD-1X1"))
    )
    (comp (ref "JP102")
      (value "PINHD-1X1")
      (footprint "eagle-import:1X01")
      (libsource (lib "eagle-import") (part "PINHD-1X1"))
    )
    (comp (ref "JP103")
      (value "PINHD-1X1")
      (footprint "eagle-import:1X01")
      (libsource (lib "eagle-import") (part "PINHD-1X1"))
    )
    (comp (ref "JP104")
      (value "PINHD-1X1")
      (footprint "eagle-import:1X01")
      (libsource (lib "eagle-import") (part "PINHD-1X1"))
    )
    (comp (ref "JP105")
      (value "PINHD-1X1")
      (footprint "eagle-import:1X01")
      (libsource (lib "eagle-import") (part "PINHD-1X1"))
    )
    (comp (ref "JP106")
      (value "PINHD-1X1")
      (footprint "eagle-import:1X01")
      (libsource (lib "eagle-import") (part "PINHD-1X1"))
    )
    (comp (ref "JP107")
      (value "PINHD-1X1")
      (footprint "eagle-import:1X01")
      (libsource (lib "eagle-import") (part "PINHD-1X1"))
    )
    (comp (ref "JP108")
      (value "PINHD-1X1")
      (footprint "eagle-import:1X01")
      (libsource (lib "eagle-import") (part "PINHD-1X1"))
    )
    (comp (ref "JP109")
      (value "PINHD-1X1")
      (footprint "eagle-import:1X01")
      (libsource (lib "eagle-import") (part "PINHD-1X1"))
    )
    (comp (ref "JP110")
      (value "PINHD-1X1")
      (footprint "eagle-import:1X01")
      (libsource (lib "eagle-import") (part "PINHD-1X1"))
    )
    (comp (ref "JP111")
      (value "PINHD-1X1")
      (footprint "eagle-import:1X01")
      (libsource (lib "eagle-import") (part "PINHD-1X1"))
    )
    (comp (ref "JP112")
      (value "PINHD-1X1")
      (footprint "eagle-import:1X01")
      (libsource (lib "eagle-import") (part "PINHD-1X1"))
    )
    (comp (ref "JP113")
      (value "PINHD-1X1")
      (footprint "eagle-import:1X01")
      (libsource (lib "eagle-import") (part "PINHD-1X1"))
    )
    (comp (ref "JP114")
      (value "PINHD-1X1")
      (footprint "eagle-import:1X01")
      (libsource (lib "eagle-import") (part "PINHD-1X1"))
    )
    (comp (ref "JP115")
      (value "PINHD-1X1-BIGPOGO")
      (footprint "eagle-import:1X1-BIGPOGO")
      (libsource (lib "eagle-import") (part "PINHD-1X1-BIGPOGO"))
    )
    (comp (ref "JP116")
      (value "PINHD-1X1-BIGPOGO")
      (footprint "eagle-import:1X1-BIGPOGO")
      (libsource (lib "eagle-import") (part "PINHD-1X1-BIGPOGO"))
    )
    (comp (ref "JP117")
      (value "PINHD-1X1-BIGPOGO")
      (footprint "eagle-import:1X1-BIGPOGO")
      (libsource (lib "eagle-import") (part "PINHD-1X1-BIGPOGO"))
    )
    (comp (ref "JP118")
      (value "PINHD-1X1-BIGPOGO")
      (footprint "eagle-import:1X1-BIGPOGO")
      (libsource (lib "eagle-import") (part "PINHD-1X1-BIGPOGO"))
    )
    (comp (ref "JP119")
      (value "PINHD-1X1-BIGPOGO")
      (footprint "eagle-import:1X1-BIGPOGO")
      (libsource (lib "eagle-import") (part "PINHD-1X1-BIGPOGO"))
    )
    (comp (ref "JP120")
      (value "PINHD-1X1-BIGPOGO")
      (footprint "eagle-import:1X1-BIGPOGO")
      (libsource (lib "eagle-import") (part "PINHD-1X1-BIGPOGO"))
    )
    (comp (ref "JP121")
      (value "PINHD-1X1-BIGPOGO")
      (footprint "eagle-import:1X1-BIGPOGO")
      (libsource (lib "eagle-import") (part "PINHD-1X1-BIGPOGO"))
    )
    (comp (ref "JP122")
      (value "PINHD-1X1-BIGPOGO")
      (footprint "eagle-import:1X1-BIGPOGO")
      (libsource (lib "eagle-import") (part "PINHD-1X1-BIGPOGO"))
    )
    (comp (ref "JP123")
      (value "PINHD-1X1")
      (footprint "eagle-import:1X01")
      (libsource (lib "eagle-import") (part "PINHD-1X1"))
    )
    (comp (ref "JP124")
      (value "PINHD-1X1")
      (footprint "eagle-import:1X01")
      (libsource (lib "eagle-import") (part "PINHD-1X1"))
    )
    (comp (ref "JP125")
      (value "PINHD-1X1")
      (footprint "eagle-import:1X01")
      (libsource (lib "eagle-import") (part "PINHD-1X1"))
    )
    (comp (ref "JP126")
      (value "PINHD-1X1")
      (footprint "eagle-import:1X01")
      (libsource (lib "eagle-import") (part "PINHD-1X1"))
    )
    (comp (ref "JP127")
      (value "PINHD-1X1")
      (footprint "eagle-import:1X01")
      (libsource (lib "eagle-import") (part "PINHD-1X1"))
    )
    (comp (ref "JP128")
      (value "PINHD-1X1")
      (footprint "eagle-import:1X01")
      (libsource (lib "eagle-import") (part "PINHD-1X1"))
    )
    (comp (ref "JP129")
      (value "PINHD-1X1")
      (footprint "eagle-import:1X01")
      (libsource (lib "eagle-import") (part "PINHD-1X1"))
    )
    (comp (ref "JP130")
      (value "PINHD-1X1")
      (footprint "eagle-import:1X01")
      (libsource (lib "eagle-import") (part "PINHD-1X1"))
    )
    (comp (ref "JP131")
      (value "PINHD-1X1")
      (footprint "eagle-import:1X01")
      (libsource (lib "eagle-import") (part "PINHD-1X1"))
    )
    (comp (ref "JP132")
      (value "PINHD-1X1")
      (footprint "eagle-import:1X01")
      (libsource (lib "eagle-import") (part "PINHD-1X1"))
    )
    (comp (ref "JP133")
      (value "PINHD-1X1")
      (footprint "eagle-import:1X01")
      (libsource (lib "eagle-import") (part "PINHD-1X1"))
    )
    (comp (ref "JP134")
      (value "PINHD-1X1")
      (footprint "eagle-import:1X01")
      (libsource (lib "eagle-import") (part "PINHD-1X1"))
    )
    (comp (ref "JP135")
      (value "PINHD-1X1-BIGPOGO")
      (footprint "eagle-import:1X1-BIGPOGO")
      (libsource (lib "eagle-import") (part "PINHD-1X1-BIGPOGO"))
    )
    (comp (ref "JP136")
      (value "PINHD-1X1-BIGPOGO")
      (footprint "eagle-import:1X1-BIGPOGO")
      (libsource (lib "eagle-import") (part "PINHD-1X1-BIGPOGO"))
    )
    (comp (ref "JP137")
      (value "PINHD-1X1-BIGPOGO")
      (footprint "eagle-import:1X1-BIGPOGO")
      (libsource (lib "eagle-import") (part "PINHD-1X1-BIGPOGO"))
    )
    (comp (ref "JP138")
      (value "PINHD-1X1-BIGPOGO")
      (footprint "eagle-import:1X1-BIGPOGO")
      (libsource (lib "eagle-import") (part "PINHD-1X1-BIGPOGO"))
    )
    (comp (ref "JP139")
      (value "PINHD-1X1-BIGPOGO")
      (footprint "eagle-import:1X1-BIGPOGO")
      (libsource (lib "eagle-import") (part "PINHD-1X1-BIGPOGO"))
    )
    (comp (ref "JP140")
      (value "PINHD-1X1-BIGPOGO")
      (footprint "eagle-import:1X1-BIGPOGO")
      (libsource (lib "eagle-import") (part "PINHD-1X1-BIGPOGO"))
    )
    (comp (ref "JP141")
      (value "PINHD-1X1-BIGPOGO")
      (footprint "eagle-import:1X1-BIGPOGO")
      (libsource (lib "eagle-import") (part "PINHD-1X1-BIGPOGO"))
    )
    (comp (ref "JP142")
      (value "PINHD-1X1-BIGPOGO")
      (footprint "eagle-import:1X1-BIGPOGO")
      (libsource (lib "eagle-import") (part "PINHD-1X1-BIGPOGO"))
    )
    (comp (ref "L2")
      (value "SMMS1770-470M")
      (footprint "eagle-import:PA4344-17X17")
      (fields (field (name "MF") "Pulse Electronics") (field (name "MPN") "PA4344.471ANLT"))
      (libsource (lib "eagle-import") (part "INDUCTORPA4344471"))
    )
    (comp (ref "PS1")
      (value "B0515S-2WR3")
      (footprint "eagle-import:B1212S2WR3")
      (fields (field (name "MANUFACTURER_PART_NUMBER") "B1212S-2WR3"))
      (libsource (lib "eagle-import") (part "B1212S-2WR3"))
    )
    (comp (ref "PS2")
      (value "B0515S-2WR3")
      (footprint "eagle-import:B1212S2WR3")
      (fields (field (name "MANUFACTURER_PART_NUMBER") "B1212S-2WR3"))
      (libsource (lib "eagle-import") (part "B1212S-2WR3"))
    )
    (comp (ref "PS7")
      (value "B0515S-2WR3")
      (footprint "eagle-import:B1212S2WR3")
      (fields (field (name "MANUFACTURER_PART_NUMBER") "B1212S-2WR3"))
      (libsource (lib "eagle-import") (part "B1212S-2WR3"))
    )
    (comp (ref "PS8")
      (value "B0515S-2WR3")
      (footprint "eagle-import:B1212S2WR3")
      (fields (field (name "MANUFACTURER_PART_NUMBER") "B1212S-2WR3"))
      (libsource (lib "eagle-import") (part "B1212S-2WR3"))
    )
    (comp (ref "Q1")
      (value "AO3400A")
      (footprint "eagle-import:SOT23")
      (libsource (lib "eagle-import") (part "MOSFET-NREFLOW"))
    )
    (comp (ref "Q2")
      (value "AO3400A")
      (footprint "eagle-import:SOT23")
      (libsource (lib "eagle-import") (part "MOSFET-NREFLOW"))
    )
    (comp (ref "Q3")
      (value "AO3400A")
      (footprint "eagle-import:SOT23")
      (libsource (lib "eagle-import") (part "MOSFET-NREFLOW"))
    )
    (comp (ref "Q4")
      (value "AO3400A")
      (footprint "eagle-import:SOT23")
      (libsource (lib "eagle-import") (part "MOSFET-NREFLOW"))
    )
    (comp (ref "Q5")
      (value "AO3400A")
      (footprint "eagle-import:SOT23")
      (libsource (lib "eagle-import") (part "MOSFET-NREFLOW"))
    )
    (comp (ref "Q6")
      (value "HSU4119")
      (footprint "eagle-import:TO252")
      (libsource (lib "eagle-import") (part "PMOS-DPAK"))
    )
    (comp (ref "Q7")
      (value "HSU4119")
      (footprint "eagle-import:TO252")
      (libsource (lib "eagle-import") (part "PMOS-DPAK"))
    )
    (comp (ref "Q8")
      (value "20V/4.2A/52mΩ/1.4W")
      (footprint "eagle-import:SOT23-3")
      (libsource (lib "eagle-import") (part "MOSFET_PCH-DMG2305UX-7"))
    )
    (comp (ref "Q9")
      (value "DOD120N04")
      (footprint "eagle-import:DPAK")
      (fields
        (field (name "DIGIKEY_PART_NUMBER") "497-STD35NF06T4CT-ND")
        (field (name "MANUFACTURER") "STMicroelectronics")
        (field (name "MPN") "STD35NF06T4")
        (field (name "CREATED_BY") "PCBLayout.com")
      )
      (libsource (lib "eagle-import") (part "STD35NF06T4"))
    )
    (comp (ref "Q10")
      (value "DOD120N04")
      (footprint "eagle-import:DPAK")
      (fields
        (field (name "DIGIKEY_PART_NUMBER") "497-STD35NF06T4CT-ND")
        (field (name "MANUFACTURER") "STMicroelectronics")
        (field (name "MPN") "STD35NF06T4")
        (field (name "CREATED_BY") "PCBLayout.com")
      )
      (libsource (lib "eagle-import") (part "STD35NF06T4"))
    )
    (comp (ref "Q11")
      (value "DOD120N04")
      (footprint "eagle-import:TO252")
      (libsource (lib "eagle-import") (part "NMOS-TO252"))
    )
    (comp (ref "Q12")
      (value "HSU4119")
      (footprint "eagle-import:TO252")
      (libsource (lib "eagle-import") (part "PMOS-DPAK"))
    )
    (comp (ref "Q13")
      (value "HSU4119")
      (footprint "eagle-import:TO252")
      (libsource (lib "eagle-import") (part "PMOS-DPAK"))
    )
    (comp (ref "Q14")
      (value "HSU4119")
      (footprint "eagle-import:TO252")
      (libsource (lib "eagle-import") (part "PMOS-DPAK"))
    )
    (comp (ref "Q15")
      (value "HSU4119")
      (footprint "eagle-import:TO252")
      (libsource (lib "eagle-import") (part "PMOS-DPAK"))
    )
    (comp (ref "Q16")
      (value "HSU4119")
      (footprint "eagle-import:TO252")
      (libsource (lib "eagle-import") (part "PMOS-DPAK"))
    )
    (comp (ref "Q17")
      (value "HSU4119")
      (footprint "eagle-import:TO252")
      (libsource (lib "eagle-import") (part "PMOS-DPAK"))
    )
    (comp (ref "Q18")
      (value "HSU4119")
      (footprint "eagle-import:TO252")
      (libsource (lib "eagle-import") (part "PMOS-DPAK"))
    )
    (comp (ref "Q19")
      (value "HSU4119")
      (footprint "eagle-import:TO252")
      (libsource (lib "eagle-import") (part "PMOS-DPAK"))
    )
    (comp (ref "Q20")
      (value "HSU4119")
      (footprint "eagle-import:TO252")
      (libsource (lib "eagle-import") (part "PMOS-DPAK"))
    )
    (comp (ref "Q21")
      (value "HSU4119")
      (footprint "eagle-import:TO252")
      (libsource (lib "eagle-import") (part "PMOS-DPAK"))
    )
    (comp (ref "Q22")
      (value "HSU4119")
      (footprint "eagle-import:TO252")
      (libsource (lib "eagle-import") (part "PMOS-DPAK"))
    )
    (comp (ref "Q23")
      (value "HSU4119")
      (footprint "eagle-import:TO252")
      (libsource (lib "eagle-import") (part "PMOS-DPAK"))
    )
    (comp (ref "Q24")
      (value "HSU4119")
      (footprint "eagle-import:TO252")
      (libsource (lib "eagle-import") (part "PMOS-DPAK"))
    )
    (comp (ref "Q25")
      (value "HSU4119")
      (footprint "eagle-import:TO252")
      (libsource (lib "eagle-import") (part "PMOS-DPAK"))
    )
    (comp (ref "Q26")
      (value "HSU4119")
      (footprint "eagle-import:TO252")
      (libsource (lib "eagle-import") (part "PMOS-DPAK"))
    )
    (comp (ref "Q27")
      (value "HSU4119")
      (footprint "eagle-import:TO252")
      (libsource (lib "eagle-import") (part "PMOS-DPAK"))
    )
    (comp (ref "Q28")
      (value "HSU4119")
      (footprint "eagle-import:TO252")
      (libsource (lib "eagle-import") (part "PMOS-DPAK"))
    )
    (comp (ref "Q29")
      (value "HSU4119")
      (footprint "eagle-import:TO252")
      (libsource (lib "eagle-import") (part "PMOS-DPAK"))
    )
    (comp (ref "Q30")
      (value "DOD120N04")
      (footprint "eagle-import:TO252")
      (libsource (lib "eagle-import") (part "NMOS-TO252"))
    )
    (comp (ref "Q31")
      (value "DOD120N04")
      (footprint "eagle-import:TO252")
      (libsource (lib "eagle-import") (part "NMOS-TO252"))
    )
    (comp (ref "Q32")
      (value "DOD120N04")
      (footprint "eagle-import:TO252")
      (libsource (lib "eagle-import") (part "NMOS-TO252"))
    )
    (comp (ref "Q33")
      (value "DOD120N04")
      (footprint "eagle-import:TO252")
      (libsource (lib "eagle-import") (part "NMOS-TO252"))
    )
    (comp (ref "Q34")
      (value "DOD120N04")
      (footprint "eagle-import:TO252")
      (libsource (lib "eagle-import") (part "NMOS-TO252"))
    )
    (comp (ref "Q35")
      (value "DOD120N04")
      (footprint "eagle-import:TO252")
      (libsource (lib "eagle-import") (part "NMOS-TO252"))
    )
    (comp (ref "Q36")
      (value "DOD120N04")
      (footprint "eagle-import:TO252")
      (libsource (lib "eagle-import") (part "NMOS-TO252"))
    )
    (comp (ref "Q37")
      (value "DOD120N04")
      (footprint "eagle-import:TO252")
      (libsource (lib "eagle-import") (part "NMOS-TO252"))
    )
    (comp (ref "Q38")
      (value "DOD120N04")
      (footprint "eagle-import:TO252")
      (libsource (lib "eagle-import") (part "NMOS-TO252"))
    )
    (comp (ref "Q39")
      (value "DOD120N04")
      (footprint "eagle-import:TO252")
      (libsource (lib "eagle-import") (part "NMOS-TO252"))
    )
    (comp (ref "Q40")
      (value "DOD120N04")
      (footprint "eagle-import:TO252")
      (libsource (lib "eagle-import") (part "NMOS-TO252"))
    )
    (comp (ref "Q41")
      (value "DOD120N04")
      (footprint "eagle-import:TO252")
      (libsource (lib "eagle-import") (part "NMOS-TO252"))
    )
    (comp (ref "Q42")
      (value "DOD120N04")
      (footprint "eagle-import:TO252")
      (libsource (lib "eagle-import") (part "NMOS-TO252"))
    )
    (comp (ref "Q43")
      (value "DOD120N04")
      (footprint "eagle-import:TO252")
      (libsource (lib "eagle-import") (part "NMOS-TO252"))
    )
    (comp (ref "Q44")
      (value "DOD120N04")
      (footprint "eagle-import:TO252")
      (libsource (lib "eagle-import") (part "NMOS-TO252"))
    )
    (comp (ref "Q45")
      (value "DOD120N04")
      (footprint "eagle-import:TO252")
      (libsource (lib "eagle-import") (part "NMOS-TO252"))
    )
    (comp (ref "Q46")
      (value "DOD120N04")
      (footprint "eagle-import:TO252")
      (libsource (lib "eagle-import") (part "NMOS-TO252"))
    )
    (comp (ref "Q47")
      (value "DOD120N04")
      (footprint "eagle-import:TO252")
      (libsource (lib "eagle-import") (part "NMOS-TO252"))
    )
    (comp (ref "Q48")
      (value "DOD120N04")
      (footprint "eagle-import:TO252")
      (libsource (lib "eagle-import") (part "NMOS-TO252"))
    )
    (comp (ref "Q49")
      (value "DOD120N04")
      (footprint "eagle-import:TO252")
      (libsource (lib "eagle-import") (part "NMOS-TO252"))
    )
    (comp (ref "Q50")
      (value "DOD120N04")
      (footprint "eagle-import:TO252")
      (libsource (lib "eagle-import") (part "NMOS-TO252"))
    )
    (comp (ref "Q51")
      (value "DOD120N04")
      (footprint "eagle-import:TO252")
      (libsource (lib "eagle-import") (part "NMOS-TO252"))
    )
    (comp (ref "Q52")
      (value "DOD120N04")
      (footprint "eagle-import:TO252")
      (libsource (lib "eagle-import") (part "NMOS-TO252"))
    )
    (comp (ref "Q53")
      (value "DOD120N04")
      (footprint "eagle-import:TO252")
      (libsource (lib "eagle-import") (part "NMOS-TO252"))
    )
    (comp (ref "Q54")
      (value "DOD120N04")
      (footprint "eagle-import:TO252")
      (libsource (lib "eagle-import") (part "NMOS-TO252"))
    )
    (comp (ref "Q55")
      (value "DOD120N04")
      (footprint "eagle-import:TO252")
      (libsource (lib "eagle-import") (part "NMOS-TO252"))
    )
    (comp (ref "Q56")
      (value "DOD120N04")
      (footprint "eagle-import:TO252")
      (libsource (lib "eagle-import") (part "NMOS-TO252"))
    )
    (comp (ref "R1")
      (value "510k")
      (footprint "eagle-import:R0603")
      (libsource (lib "eagle-import") (part "rcl_334_R-EU_R0603"))
    )
    (comp (ref "R2")
      (value "10k")
      (footprint "eagle-import:R0805")
      (libsource (lib "eagle-import") (part "rcl_334_R-EU_R0805"))
    )
    (comp (ref "R3")
      (value "470")
      (footprint "eagle-import:R0805")
      (libsource (lib "eagle-import") (part "rcl_334_R-EU_R0805"))
    )
    (comp (ref "R4")
      (value "10k")
      (footprint "eagle-import:R0805")
      (libsource (lib "eagle-import") (part "rcl_334_R-EU_R0805"))
    )
    (comp (ref "R5")
      (value "470")
      (footprint "eagle-import:R0805")
      (libsource (lib "eagle-import") (part "rcl_334_R-EU_R0805"))
    )
    (comp (ref "R6")
      (value "10k")
      (footprint "eagle-import:R0805")
      (libsource (lib "eagle-import") (part "rcl_334_R-EU_R0805"))
    )
    (comp (ref "R7")
      (value "470")
      (footprint "eagle-import:R0805")
      (libsource (lib "eagle-import") (part "rcl_334_R-EU_R0805"))
    )
    (comp (ref "R8")
      (value "4.7k")
      (footprint "eagle-import:R0402")
      (libsource (lib "eagle-import") (part "rcl_334_R-EU_R0402"))
    )
    (comp (ref "R9")
      (value "4.7k")
      (footprint "eagle-import:R0402")
      (libsource (lib "eagle-import") (part "rcl_334_R-EU_R0402"))
    )
    (comp (ref "R10")
      (value "100")
      (footprint "eagle-import:R1206")
      (libsource (lib "eagle-import") (part "rcl_334_R-EU_R1206"))
    )
    (comp (ref "R11")
      (value "100")
      (footprint "eagle-import:R1206")
      (libsource (lib "eagle-import") (part "rcl_334_R-EU_R1206"))
    )
    (comp (ref "R12")
      (value "100")
      (footprint "eagle-import:R1206")
      (libsource (lib "eagle-import") (part "rcl_334_R-EU_R1206"))
    )
    (comp (ref "R13")
      (value "100")
      (footprint "eagle-import:R1206")
      (libsource (lib "eagle-import") (part "rcl_334_R-EU_R1206"))
    )
    (comp (ref "R14")
      (value "100")
      (footprint "eagle-import:R1206")
      (libsource (lib "eagle-import") (part "rcl_334_R-EU_R1206"))
    )
    (comp (ref "R15")
      (value "100")
      (footprint "eagle-import:R1206")
      (libsource (lib "eagle-import") (part "rcl_334_R-EU_R1206"))
    )
    (comp (ref "R16")
      (value "15R, 1W")
      (footprint "eagle-import:R2512")
      (libsource (lib "eagle-import") (part "rcl_334_R-EU_R2512"))
    )
    (comp (ref "R17")
      (value "1k")
      (footprint "eagle-import:R0402")
      (libsource (lib "eagle-import") (part "R-EU_R0402"))
    )
    (comp (ref "R18")
      (value "10k")
      (footprint "eagle-import:R0402")
      (libsource (lib "eagle-import") (part "R-EU_R0402"))
    )
    (comp (ref "R19")
      (value "15R, 1W")
      (footprint "eagle-import:R2512")
      (libsource (lib "eagle-import") (part "rcl_334_R-EU_R2512"))
    )
    (comp (ref "R20")
      (value "1k")
      (footprint "eagle-import:R0402")
      (libsource (lib "eagle-import") (part "R-EU_R0402"))
    )
    (comp (ref "R21")
      (value "10k")
      (footprint "eagle-import:R0402")
      (libsource (lib "eagle-import") (part "R-EU_R0402"))
    )
    (comp (ref "R22")
      (value "15R, 1W")
      (footprint "eagle-import:R2512")
      (libsource (lib "eagle-import") (part "rcl_334_R-EU_R2512"))
    )
    (comp (ref "R23")
      (value "1k")
      (footprint "eagle-import:R0402")
      (libsource (lib "eagle-import") (part "R-EU_R0402"))
    )
    (comp (ref "R24")
      (value "10k")
      (footprint "eagle-import:R0402")
      (libsource (lib "eagle-import") (part "R-EU_R0402"))
    )
    (comp (ref "R25")
      (value "15R, 1W")
      (footprint "eagle-import:R2512")
      (libsource (lib "eagle-import") (part "rcl_334_R-EU_R2512"))
    )
    (comp (ref "R26")
      (value "1k")
      (footprint "eagle-import:R0402")
      (libsource (lib "eagle-import") (part "R-EU_R0402"))
    )
    (comp (ref "R27")
      (value "10k")
      (footprint "eagle-import:R0402")
      (libsource (lib "eagle-import") (part "R-EU_R0402"))
    )
    (comp (ref "R28")
      (value "15R, 1W")
      (footprint "eagle-import:R2512")
      (libsource (lib "eagle-import") (part "rcl_334_R-EU_R2512"))
    )
    (comp (ref "R29")
      (value "1k")
      (footprint "eagle-import:R0402")
      (libsource (lib "eagle-import") (part "R-EU_R0402"))
    )
    (comp (ref "R30")
      (value "10k")
      (footprint "eagle-import:R0402")
      (libsource (lib "eagle-import") (part "R-EU_R0402"))
    )
    (comp (ref "R31")
      (value "100")
      (footprint "eagle-import:R0805")
      (libsource (lib "eagle-import") (part "R-EU_R0805"))
    )
    (comp (ref "R32")
      (value "WSL25121L000FEA18")
      (footprint "eagle-import:R2512")
      (libsource (lib "eagle-import") (part "rcl_334_R-EU_R2512"))
    )
    (comp (ref "R33")
      (value "100")
      (footprint "eagle-import:R0805")
      (libsource (lib "eagle-import") (part "R-EU_R0805"))
    )
    (comp (ref "R34")
      (value "1M")
      (footprint "eagle-import:R0805")
      (libsource (lib "eagle-import") (part "rcl_334_R-EU_R0805"))
    )
    (comp (ref "R35")
      (value "1M")
      (footprint "eagle-import:R0805")
      (libsource (lib "eagle-import") (part "rcl_334_R-EU_R0805"))
    )
    (comp (ref "R36")
      (value "1M")
      (footprint "eagle-import:R0805")
      (libsource (lib "eagle-import") (part "rcl_334_R-EU_R0805"))
    )
    (comp (ref "R37")
      (value "100")
      (footprint "eagle-import:R1206")
      (libsource (lib "eagle-import") (part "rcl_334_R-EU_R1206"))
    )
    (comp (ref "R38")
      (value "10k")
      (footprint "eagle-import:R0402")
      (libsource (lib "eagle-import") (part "R-EU_R0402"))
    )
    (comp (ref "R39")
      (value "10k")
      (footprint "eagle-import:R0805")
      (libsource (lib "eagle-import") (part "rcl_334_R-EU_R0805"))
    )
    (comp (ref "R40")
      (value "470")
      (footprint "eagle-import:R0805")
      (libsource (lib "eagle-import") (part "rcl_334_R-EU_R0805"))
    )
    (comp (ref "R41")
      (value "220")
      (footprint "eagle-import:R0805")
      (libsource (lib "eagle-import") (part "rcl_334_R-EU_R0805"))
    )
    (comp (ref "R42")
      (value "220")
      (footprint "eagle-import:R0805")
      (libsource (lib "eagle-import") (part "rcl_334_R-EU_R0805"))
    )
    (comp (ref "R43")
      (value "220")
      (footprint "eagle-import:R0805")
      (libsource (lib "eagle-import") (part "rcl_334_R-EU_R0805"))
    )
    (comp (ref "R44")
      (value "220")
      (footprint "eagle-import:R0805")
      (libsource (lib "eagle-import") (part "rcl_334_R-EU_R0805"))
    )
    (comp (ref "R45")
      (value "10k")
      (footprint "eagle-import:R0805")
      (libsource (lib "eagle-import") (part "rcl_334_R-EU_R0805"))
    )
    (comp (ref "R46")
      (value "470")
      (footprint "eagle-import:R0805")
      (libsource (lib "eagle-import") (part "rcl_334_R-EU_R0805"))
    )
    (comp (ref "R47")
      (value "10k")
      (footprint "eagle-import:R0805")
      (libsource (lib "eagle-import") (part "rcl_334_R-EU_R0805"))
    )
    (comp (ref "R48")
      (value "470")
      (footprint "eagle-import:R0805")
      (libsource (lib "eagle-import") (part "rcl_334_R-EU_R0805"))
    )
    (comp (ref "R49")
      (value "10k")
      (footprint "eagle-import:R0805")
      (libsource (lib "eagle-import") (part "rcl_334_R-EU_R0805"))
    )
    (comp (ref "R50")
      (value "470")
      (footprint "eagle-import:R0805")
      (libsource (lib "eagle-import") (part "rcl_334_R-EU_R0805"))
    )
    (comp (ref "R51")
      (value "10k")
      (footprint "eagle-import:R0805")
      (libsource (lib "eagle-import") (part "rcl_334_R-EU_R0805"))
    )
    (comp (ref "R52")
      (value "470")
      (footprint "eagle-import:R0805")
      (libsource (lib "eagle-import") (part "rcl_334_R-EU_R0805"))
    )
    (comp (ref "R53")
      (value "220")
      (footprint "eagle-import:R0805")
      (libsource (lib "eagle-import") (part "rcl_334_R-EU_R0805"))
    )
    (comp (ref "R54")
      (value "220")
      (footprint "eagle-import:R0805")
      (libsource (lib "eagle-import") (part "rcl_334_R-EU_R0805"))
    )
    (comp (ref "R55")
      (value "220")
      (footprint "eagle-import:R0805")
      (libsource (lib "eagle-import") (part "rcl_334_R-EU_R0805"))
    )
    (comp (ref "R56")
      (value "220")
      (footprint "eagle-import:R0805")
      (libsource (lib "eagle-import") (part "rcl_334_R-EU_R0805"))
    )
    (comp (ref "R57")
      (value "10k")
      (footprint "eagle-import:R0805")
      (libsource (lib "eagle-import") (part "rcl_334_R-EU_R0805"))
    )
    (comp (ref "R58")
      (value "470")
      (footprint "eagle-import:R0805")
      (libsource (lib "eagle-import") (part "rcl_334_R-EU_R0805"))
    )
    (comp (ref "R59")
      (value "10k")
      (footprint "eagle-import:R0805")
      (libsource (lib "eagle-import") (part "rcl_334_R-EU_R0805"))
    )
    (comp (ref "R60")
      (value "470")
      (footprint "eagle-import:R0805")
      (libsource (lib "eagle-import") (part "rcl_334_R-EU_R0805"))
    )
    (comp (ref "R61")
      (value "10k")
      (footprint "eagle-import:R0805")
      (libsource (lib "eagle-import") (part "rcl_334_R-EU_R0805"))
    )
    (comp (ref "R62")
      (value "470")
      (footprint "eagle-import:R0805")
      (libsource (lib "eagle-import") (part "rcl_334_R-EU_R0805"))
    )
    (comp (ref "R63")
      (value "10k")
      (footprint "eagle-import:R0805")
      (libsource (lib "eagle-import") (part "rcl_334_R-EU_R0805"))
    )
    (comp (ref "R64")
      (value "470")
      (footprint "eagle-import:R0805")
      (libsource (lib "eagle-import") (part "rcl_334_R-EU_R0805"))
    )
    (comp (ref "R65")
      (value "220")
      (footprint "eagle-import:R0805")
      (libsource (lib "eagle-import") (part "rcl_334_R-EU_R0805"))
    )
    (comp (ref "R66")
      (value "220")
      (footprint "eagle-import:R0805")
      (libsource (lib "eagle-import") (part "rcl_334_R-EU_R0805"))
    )
    (comp (ref "R67")
      (value "220")
      (footprint "eagle-import:R0805")
      (libsource (lib "eagle-import") (part "rcl_334_R-EU_R0805"))
    )
    (comp (ref "R68")
      (value "220")
      (footprint "eagle-import:R0805")
      (libsource (lib "eagle-import") (part "rcl_334_R-EU_R0805"))
    )
    (comp (ref "R69")
      (value "10k")
      (footprint "eagle-import:R0805")
      (libsource (lib "eagle-import") (part "rcl_334_R-EU_R0805"))
    )
    (comp (ref "R70")
      (value "470")
      (footprint "eagle-import:R0805")
      (libsource (lib "eagle-import") (part "rcl_334_R-EU_R0805"))
    )
    (comp (ref "R71")
      (value "10k")
      (footprint "eagle-import:R0805")
      (libsource (lib "eagle-import") (part "rcl_334_R-EU_R0805"))
    )
    (comp (ref "R72")
      (value "470")
      (footprint "eagle-import:R0805")
      (libsource (lib "eagle-import") (part "rcl_334_R-EU_R0805"))
    )
    (comp (ref "R73")
      (value "10k")
      (footprint "eagle-import:R0805")
      (libsource (lib "eagle-import") (part "rcl_334_R-EU_R0805"))
    )
    (comp (ref "R74")
      (value "470")
      (footprint "eagle-import:R0805")
      (libsource (lib "eagle-import") (part "rcl_334_R-EU_R0805"))
    )
    (comp (ref "R75")
      (value "10k")
      (footprint "eagle-import:R0805")
      (libsource (lib "eagle-import") (part "rcl_334_R-EU_R0805"))
    )
    (comp (ref "R76")
      (value "470")
      (footprint "eagle-import:R0805")
      (libsource (lib "eagle-import") (part "rcl_334_R-EU_R0805"))
    )
    (comp (ref "R77")
      (value "220")
      (footprint "eagle-import:R0805")
      (libsource (lib "eagle-import") (part "rcl_334_R-EU_R0805"))
    )
    (comp (ref "R78")
      (value "220")
      (footprint "eagle-import:R0805")
      (libsource (lib "eagle-import") (part "rcl_334_R-EU_R0805"))
    )
    (comp (ref "R79")
      (value "220")
      (footprint "eagle-import:R0805")
      (libsource (lib "eagle-import") (part "rcl_334_R-EU_R0805"))
    )
    (comp (ref "R80")
      (value "220")
      (footprint "eagle-import:R0805")
      (libsource (lib "eagle-import") (part "rcl_334_R-EU_R0805"))
    )
    (comp (ref "R81")
      (value "10k")
      (footprint "eagle-import:R0805")
      (libsource (lib "eagle-import") (part "rcl_334_R-EU_R0805"))
    )
    (comp (ref "R82")
      (value "470")
      (footprint "eagle-import:R0805")
      (libsource (lib "eagle-import") (part "rcl_334_R-EU_R0805"))
    )
    (comp (ref "R83")
      (value "10k")
      (footprint "eagle-import:R0805")
      (libsource (lib "eagle-import") (part "rcl_334_R-EU_R0805"))
    )
    (comp (ref "R84")
      (value "470")
      (footprint "eagle-import:R0805")
      (libsource (lib "eagle-import") (part "rcl_334_R-EU_R0805"))
    )
    (comp (ref "R85")
      (value "10k")
      (footprint "eagle-import:R0805")
      (libsource (lib "eagle-import") (part "rcl_334_R-EU_R0805"))
    )
    (comp (ref "R86")
      (value "470")
      (footprint "eagle-import:R0805")
      (libsource (lib "eagle-import") (part "rcl_334_R-EU_R0805"))
    )
    (comp (ref "R87")
      (value "10k")
      (footprint "eagle-import:R0805")
      (libsource (lib "eagle-import") (part "rcl_334_R-EU_R0805"))
    )
    (comp (ref "R88")
      (value "470")
      (footprint "eagle-import:R0805")
      (libsource (lib "eagle-import") (part "rcl_334_R-EU_R0805"))
    )
    (comp (ref "R89")
      (value "220")
      (footprint "eagle-import:R0805")
      (libsource (lib "eagle-import") (part "rcl_334_R-EU_R0805"))
    )
    (comp (ref "R90")
      (value "220")
      (footprint "eagle-import:R0805")
      (libsource (lib "eagle-import") (part "rcl_334_R-EU_R0805"))
    )
    (comp (ref "R91")
      (value "220")
      (footprint "eagle-import:R0805")
      (libsource (lib "eagle-import") (part "rcl_334_R-EU_R0805"))
    )
    (comp (ref "R92")
      (value "220")
      (footprint "eagle-import:R0805")
      (libsource (lib "eagle-import") (part "rcl_334_R-EU_R0805"))
    )
    (comp (ref "R93")
      (value "200")
      (footprint "eagle-import:R0805")
      (libsource (lib "eagle-import") (part "rcl_334_R-EU_R0805"))
    )
    (comp (ref "R94")
      (value "10")
      (footprint "eagle-import:R1206")
      (libsource (lib "eagle-import") (part "rcl_334_R-EU_R1206"))
    )
    (comp (ref "R95")
      (value "10k")
      (footprint "eagle-import:R0805")
      (libsource (lib "eagle-import") (part "rcl_334_R-EU_R0805"))
    )
    (comp (ref "R96")
      (value "EMPTY")
      (footprint "eagle-import:R1206")
      (libsource (lib "eagle-import") (part "rcl_334_R-EU_R1206"))
    )
    (comp (ref "R97")
      (value "EMPTY")
      (footprint "eagle-import:R1206")
      (libsource (lib "eagle-import") (part "rcl_334_R-EU_R1206"))
    )
    (comp (ref "R98")
      (value "200")
      (footprint "eagle-import:R0805")
      (libsource (lib "eagle-import") (part "rcl_334_R-EU_R0805"))
    )
    (comp (ref "R99")
      (value "10")
      (footprint "eagle-import:R1206")
      (libsource (lib "eagle-import") (part "rcl_334_R-EU_R1206"))
    )
    (comp (ref "R100")
      (value "10k")
      (footprint "eagle-import:R0805")
      (libsource (lib "eagle-import") (part "rcl_334_R-EU_R0805"))
    )
    (comp (ref "R101")
      (value "EMPTY")
      (footprint "eagle-import:R1206")
      (libsource (lib "eagle-import") (part "rcl_334_R-EU_R1206"))
    )
    (comp (ref "R102")
      (value "EMPTY")
      (footprint "eagle-import:R1206")
      (libsource (lib "eagle-import") (part "rcl_334_R-EU_R1206"))
    )
    (comp (ref "R103")
      (value "200")
      (footprint "eagle-import:R0805")
      (libsource (lib "eagle-import") (part "rcl_334_R-EU_R0805"))
    )
    (comp (ref "R104")
      (value "10")
      (footprint "eagle-import:R1206")
      (libsource (lib "eagle-import") (part "rcl_334_R-EU_R1206"))
    )
    (comp (ref "R105")
      (value "10k")
      (footprint "eagle-import:R0805")
      (libsource (lib "eagle-import") (part "rcl_334_R-EU_R0805"))
    )
    (comp (ref "R106")
      (value "EMPTY")
      (footprint "eagle-import:R1206")
      (libsource (lib "eagle-import") (part "rcl_334_R-EU_R1206"))
    )
    (comp (ref "R107")
      (value "EMPTY")
      (footprint "eagle-import:R1206")
      (libsource (lib "eagle-import") (part "rcl_334_R-EU_R1206"))
    )
    (comp (ref "R108")
      (value "200")
      (footprint "eagle-import:R0805")
      (libsource (lib "eagle-import") (part "rcl_334_R-EU_R0805"))
    )
    (comp (ref "R109")
      (value "10")
      (footprint "eagle-import:R1206")
      (libsource (lib "eagle-import") (part "rcl_334_R-EU_R1206"))
    )
    (comp (ref "R110")
      (value "10k")
      (footprint "eagle-import:R0805")
      (libsource (lib "eagle-import") (part "rcl_334_R-EU_R0805"))
    )
    (comp (ref "R111")
      (value "EMPTY")
      (footprint "eagle-import:R1206")
      (libsource (lib "eagle-import") (part "rcl_334_R-EU_R1206"))
    )
    (comp (ref "R112")
      (value "EMPTY")
      (footprint "eagle-import:R1206")
      (libsource (lib "eagle-import") (part "rcl_334_R-EU_R1206"))
    )
    (comp (ref "R113")
      (value "220")
      (footprint "eagle-import:R0805")
      (libsource (lib "eagle-import") (part "R-EU_R0805"))
    )
    (comp (ref "R114")
      (value "220")
      (footprint "eagle-import:R0805")
      (libsource (lib "eagle-import") (part "R-EU_R0805"))
    )
    (comp (ref "S2")
      (value "MOMENTARY-SWITCH-SPST-SMD-5.2-TALL-REDUNDANT")
      (footprint "eagle-import:TACTILE_SWITCH_SMD_5.2MM")
      (libsource (lib "eagle-import") (part "MOMENTARY-SWITCH-SPST-SMD-5.2-TALL-REDUNDANT"))
    )
    (comp (ref "SW1")
      (value "SW_DIP-1")
      (footprint "eagle-import:EDG-01")
      (libsource (lib "eagle-import") (part "SW_DIP-1"))
    )
    (comp (ref "U1")
      (value "BQ76920")
      (footprint "eagle-import:TSSOP-20_4.4X6.5MM_PITCH0.65MM")
      (libsource (lib "eagle-import") (part "BQ76920"))
    )
  )
  (nets
    (net (code "1") (name "3.3V") (class "Default")
      (node (ref "C24") (pin "1") (pinfunction "1_1") (pintype "passive"))
      (node (ref "JP1") (pin "1") (pinfunction "1_1") (pintype "passive"))
      (node (ref "JP20") (pin "1") (pinfunction "1_1") (pintype "passive"))
      (node (ref "JP39") (pin "1") (pinfunction "1_1") (pintype "passive"))
      (node (ref "R8") (pin "1") (pinfunction "1_1") (pintype "passive"))
      (node (ref "R9") (pin "1") (pinfunction "1_1") (pintype "passive"))
      (node (ref "U1") (pin "8") (pinfunction "REGOUT_8") (pintype "bidirectional"))
    )
    (net (code "2") (name "5V") (class "Default")
      (node (ref "JP121") (pin "P$1") (pinfunction "1_P$1") (pintype "passive"))
      (node (ref "SW1") (pin "1") (pinfunction "1_1") (pintype "passive"))
    )
    (net (code "3") (name "B1") (class "Default")
      (node (ref "IC2") (pin "3") (pinfunction "E_3") (pintype "bidirectional"))
      (node (ref "IC4") (pin "3") (pinfunction "E_3") (pintype "bidirectional"))
      (node (ref "IC5") (pin "3") (pinfunction "E_3") (pintype "bidirectional"))
      (node (ref "IC7") (pin "3") (pinfunction "E_3") (pintype "bidirectional"))
      (node (ref "J4") (pin "2") (pinfunction "2_2") (pintype "passive"))
      (node (ref "J5") (pin "2") (pinfunction "2_2") (pintype "passive"))
      (node (ref "J8") (pin "2") (pinfunction "2_2") (pintype "passive"))
      (node (ref "Q33") (pin "D") (pinfunction "D_D") (pintype "passive"))
      (node (ref "Q39") (pin "D") (pinfunction "D_D") (pintype "passive"))
      (node (ref "Q4") (pin "2") (pinfunction "S_2") (pintype "bidirectional"))
      (node (ref "Q45") (pin "D") (pinfunction "D_D") (pintype "passive"))
      (node (ref "Q48") (pin "D") (pinfunction "D_D") (pintype "passive"))
      (node (ref "R14") (pin "1") (pinfunction "1_1") (pintype "passive"))
      (node (ref "R28") (pin "2") (pinfunction "2_2") (pintype "passive"))
      (node (ref "R29") (pin "2") (pinfunction "2_2") (pintype "passive"))
    )
    (net (code "4") (name "B2") (class "Default")
      (node (ref "IC1") (pin "3") (pinfunction "E_3") (pintype "bidirectional"))
      (node (ref "IC3") (pin "3") (pinfunction "E_3") (pintype "bidirectional"))
      (node (ref "J4") (pin "3") (pinfunction "3_3") (pintype "passive"))
      (node (ref "J5") (pin "3") (pinfunction "3_3") (pintype "passive"))
      (node (ref "J8") (pin "3") (pinfunction "3_3") (pintype "passive"))
      (node (ref "Q11") (pin "D") (pinfunction "D_D") (pintype "passive"))
      (node (ref "Q3") (pin "2") (pinfunction "S_2") (pintype "bidirectional"))
      (node (ref "Q31") (pin "D") (pinfunction "D_D") (pintype "passive"))
      (node (ref "Q34") (pin "D") (pinfunction "D_D") (pintype "passive"))
      (node (ref "Q37") (pin "D") (pinfunction "D_D") (pintype "passive"))
      (node (ref "R13") (pin "1") (pinfunction "1_1") (pintype "passive"))
      (node (ref "R25") (pin "2") (pinfunction "2_2") (pintype "passive"))
      (node (ref "R26") (pin "2") (pinfunction "2_2") (pintype "passive"))
    )
    (net (code "5") (name "B3") (class "Default")
      (node (ref "IC18") (pin "4") (pinfunction "C_4") (pintype "bidirectional"))
      (node (ref "IC20") (pin "4") (pinfunction "C_4") (pintype "bidirectional"))
      (node (ref "J4") (pin "4") (pinfunction "4_4") (pintype "passive"))
      (node (ref "J5") (pin "4") (pinfunction "4_4") (pintype "passive"))
      (node (ref "J8") (pin "4") (pinfunction "4_4") (pintype "passive"))
      (node (ref "Q2") (pin "2") (pinfunction "S_2") (pintype "bidirectional"))
      (node (ref "Q23") (pin "D") (pinfunction "D_D") (pintype "passive"))
      (node (ref "Q24") (pin "D") (pinfunction "D_D") (pintype "passive"))
      (node (ref "Q27") (pin "D") (pinfunction "D_D") (pintype "passive"))
      (node (ref "Q28") (pin "D") (pinfunction "D_D") (pintype "passive"))
      (node (ref "R12") (pin "1") (pinfunction "1_1") (pintype "passive"))
      (node (ref "R22") (pin "2") (pinfunction "2_2") (pintype "passive"))
      (node (ref "R23") (pin "2") (pinfunction "2_2") (pintype "passive"))
    )
    (net (code "6") (name "B4") (class "Default")
      (node (ref "IC14") (pin "4") (pinfunction "C_4") (pintype "bidirectional"))
      (node (ref "IC16") (pin "4") (pinfunction "C_4") (pintype "bidirectional"))
      (node (ref "IC17") (pin "4") (pinfunction "C_4") (pintype "bidirectional"))
      (node (ref "IC19") (pin "4") (pinfunction "C_4") (pintype "bidirectional"))
      (node (ref "J4") (pin "5") (pinfunction "5_5") (pintype "passive"))
      (node (ref "J5") (pin "5") (pinfunction "5_5") (pintype "passive"))
      (node (ref "J8") (pin "5") (pinfunction "5_5") (pintype "passive"))
      (node (ref "Q1") (pin "2") (pinfunction "S_2") (pintype "bidirectional"))
      (node (ref "Q15") (pin "D") (pinfunction "D_D") (pintype "passive"))
      (node (ref "Q16") (pin "D") (pinfunction "D_D") (pintype "passive"))
      (node (ref "Q19") (pin "D") (pinfunction "D_D") (pintype "passive"))
      (node (ref "Q20") (pin "D") (pinfunction "D_D") (pintype "passive"))
      (node (ref "R11") (pin "1") (pinfunction "1_1") (pintype "passive"))
      (node (ref "R19") (pin "2") (pinfunction "2_2") (pintype "passive"))
      (node (ref "R20") (pin "2") (pinfunction "2_2") (pintype "passive"))
    )
    (net (code "7") (name "B5") (class "Default")
      (node (ref "C22") (pin "1") (pinfunction "1_1") (pintype "passive"))
      (node (ref "C23") (pin "1") (pinfunction "1_1") (pintype "passive"))
      (node (ref "CON1") (pin "+") (pinfunction "+_+") (pintype "power_in"))
      (node (ref "CON2") (pin "+") (pinfunction "+_+") (pintype "power_in"))
      (node (ref "IC10") (pin "4") (pinfunction "C_4") (pintype "bidirectional"))
      (node (ref "IC12") (pin "4") (pinfunction "C_4") (pintype "bidirectional"))
      (node (ref "IC13") (pin "4") (pinfunction "C_4") (pintype "bidirectional"))
      (node (ref "IC15") (pin "4") (pinfunction "C_4") (pintype "bidirectional"))
      (node (ref "J4") (pin "6") (pinfunction "6_6") (pintype "passive"))
      (node (ref "J5") (pin "6") (pinfunction "6_6") (pintype "passive"))
      (node (ref "J8") (pin "6") (pinfunction "6_6") (pintype "passive"))
      (node (ref "JP115") (pin "P$1") (pinfunction "1_P$1") (pintype "passive"))
      (node (ref "JP119") (pin "P$1") (pinfunction "1_P$1") (pintype "passive"))
      (node (ref "Q12") (pin "D") (pinfunction "D_D") (pintype "passive"))
      (node (ref "Q6") (pin "D") (pinfunction "D_D") (pintype "passive"))
      (node (ref "R10") (pin "1") (pinfunction "1_1") (pintype "passive"))
      (node (ref "R16") (pin "2") (pinfunction "2_2") (pintype "passive"))
      (node (ref "R17") (pin "2") (pinfunction "2_2") (pintype "passive"))
      (node (ref "R37") (pin "1") (pinfunction "1_1") (pintype "passive"))
      (node (ref "U1") (pin "9") (pinfunction "REGSRC_9") (pintype "input"))
    )
    (net (code "8") (name "CHG") (class "Default")
      (node (ref "Q8") (pin "2") (pinfunction "S_2") (pintype "bidirectional"))
      (node (ref "U1") (pin "2") (pinfunction "CHG_2") (pintype "output"))
    )
    (net (code "9") (name "CLK") (class "Default")
      (node (ref "JP58") (pin "1") (pinfunction "1_1") (pintype "passive"))
      (node (ref "JP77") (pin "1") (pinfunction "1_1") (pintype "passive"))
      (node (ref "JP96") (pin "1") (pinfunction "1_1") (pintype "passive"))
    )
    (net (code "10") (name "CMD") (class "Default")
      (node (ref "JP18") (pin "1") (pinfunction "1_1") (pintype "passive"))
      (node (ref "JP37") (pin "1") (pinfunction "1_1") (pintype "passive"))
      (node (ref "JP56") (pin "1") (pinfunction "1_1") (pintype "passive"))
    )
    (net (code "11") (name "DSG") (class "Default")
      (node (ref "Q9") (pin "1") (pinfunction "G_1") (pintype "passive"))
      (node (ref "R34") (pin "1") (pinfunction "1_1") (pintype "passive"))
      (node (ref "U1") (pin "1") (pinfunction "DSG_1") (pintype "output"))
    )
    (net (code "12") (name "EN") (class "Default")
      (node (ref "JP2") (pin "1") (pinfunction "1_1") (pintype "passive"))
      (node (ref "JP21") (pin "1") (pinfunction "1_1") (pintype "passive"))
      (node (ref "JP40") (pin "1") (pinfunction "1_1") (pintype "passive"))
    )
    (net (code "13") (name "G0") (class "Default")
      (node (ref "JP101") (pin "1") (pinfunction "1_1") (pintype "passive"))
      (node (ref "JP63") (pin "1") (pinfunction "1_1") (pintype "passive"))
      (node (ref "JP82") (pin "1") (pinfunction "1_1") (pintype "passive"))
    )
    (net (code "14") (name "G2") (class "Default")
      (node (ref "JP100") (pin "1") (pinfunction "1_1") (pintype "passive"))
      (node (ref "JP62") (pin "1") (pinfunction "1_1") (pintype "passive"))
      (node (ref "JP81") (pin "1") (pinfunction "1_1") (pintype "passive"))
      (node (ref "R30") (pin "2") (pinfunction "2_2") (pintype "passive"))
    )
    (net (code "15") (name "G4") (class "Default")
      (node (ref "J2") (pin "1") (pinfunction "1_1") (pintype "passive"))
      (node (ref "J3") (pin "1") (pinfunction "1_1") (pintype "passive"))
      (node (ref "JP102") (pin "1") (pinfunction "1_1") (pintype "passive"))
      (node (ref "JP64") (pin "1") (pinfunction "1_1") (pintype "passive"))
      (node (ref "JP83") (pin "1") (pinfunction "1_1") (pintype "passive"))
      (node (ref "R43") (pin "2") (pinfunction "2_2") (pintype "passive"))
      (node (ref "R44") (pin "2") (pinfunction "2_2") (pintype "passive"))
    )
    (net (code "16") (name "G5") (class "Default")
      (node (ref "J2") (pin "2") (pinfunction "2_2") (pintype "passive"))
      (node (ref "J3") (pin "2") (pinfunction "2_2") (pintype "passive"))
      (node (ref "JP105") (pin "1") (pinfunction "1_1") (pintype "passive"))
      (node (ref "JP67") (pin "1") (pinfunction "1_1") (pintype "passive"))
      (node (ref "JP86") (pin "1") (pinfunction "1_1") (pintype "passive"))
      (node (ref "R55") (pin "2") (pinfunction "2_2") (pintype "passive"))
      (node (ref "R56") (pin "2") (pinfunction "2_2") (pintype "passive"))
    )
    (net (code "17") (name "G12") (class "Default")
      (node (ref "J2") (pin "3") (pinfunction "3_3") (pintype "passive"))
      (node (ref "J3") (pin "3") (pinfunction "3_3") (pintype "passive"))
      (node (ref "JP13") (pin "1") (pinfunction "1_1") (pintype "passive"))
      (node (ref "JP32") (pin "1") (pinfunction "1_1") (pintype "passive"))
      (node (ref "JP51") (pin "1") (pinfunction "1_1") (pintype "passive"))
      (node (ref "R67") (pin "2") (pinfunction "2_2") (pintype "passive"))
      (node (ref "R68") (pin "2") (pinfunction "2_2") (pintype "passive"))
    )
    (net (code "18") (name "G13") (class "Default")
      (node (ref "J2") (pin "4") (pinfunction "4_4") (pintype "passive"))
      (node (ref "J3") (pin "4") (pinfunction "4_4") (pintype "passive"))
      (node (ref "JP15") (pin "1") (pinfunction "1_1") (pintype "passive"))
      (node (ref "JP34") (pin "1") (pinfunction "1_1") (pintype "passive"))
      (node (ref "JP53") (pin "1") (pinfunction "1_1") (pintype "passive"))
      (node (ref "R79") (pin "2") (pinfunction "2_2") (pintype "passive"))
      (node (ref "R80") (pin "2") (pinfunction "2_2") (pintype "passive"))
    )
    (net (code "19") (name "G14") (class "Default")
      (node (ref "J2") (pin "5") (pinfunction "5_5") (pintype "passive"))
      (node (ref "J3") (pin "5") (pinfunction "5_5") (pintype "passive"))
      (node (ref "JP12") (pin "1") (pinfunction "1_1") (pintype "passive"))
      (node (ref "JP31") (pin "1") (pinfunction "1_1") (pintype "passive"))
      (node (ref "JP50") (pin "1") (pinfunction "1_1") (pintype "passive"))
      (node (ref "R91") (pin "2") (pinfunction "2_2") (pintype "passive"))
      (node (ref "R92") (pin "2") (pinfunction "2_2") (pintype "passive"))
    )
    (net (code "20") (name "G15") (class "Default")
      (node (ref "J2") (pin "6") (pinfunction "6_6") (pintype "passive"))
      (node (ref "J3") (pin "6") (pinfunction "6_6") (pintype "passive"))
      (node (ref "JP61") (pin "1") (pinfunction "1_1") (pintype "passive"))
      (node (ref "JP80") (pin "1") (pinfunction "1_1") (pintype "passive"))
      (node (ref "JP99") (pin "1") (pinfunction "1_1") (pintype "passive"))
      (node (ref "R41") (pin "2") (pinfunction "2_2") (pintype "passive"))
      (node (ref "R42") (pin "2") (pinfunction "2_2") (pintype "passive"))
    )
    (net (code "21") (name "G16") (class "Default")
      (node (ref "J2") (pin "7") (pinfunction "7_7") (pintype "passive"))
      (node (ref "J3") (pin "7") (pinfunction "7_7") (pintype "passive"))
      (node (ref "JP103") (pin "1") (pinfunction "1_1") (pintype "passive"))
      (node (ref "JP65") (pin "1") (pinfunction "1_1") (pintype "passive"))
      (node (ref "JP84") (pin "1") (pinfunction "1_1") (pintype "passive"))
      (node (ref "R53") (pin "2") (pinfunction "2_2") (pintype "passive"))
      (node (ref "R54") (pin "2") (pinfunction "2_2") (pintype "passive"))
    )
    (net (code "22") (name "G17") (class "Default")
      (node (ref "J2") (pin "8") (pinfunction "8_8") (pintype "passive"))
      (node (ref "J3") (pin "8") (pinfunction "8_8") (pintype "passive"))
      (node (ref "JP104") (pin "1") (pinfunction "1_1") (pintype "passive"))
      (node (ref "JP66") (pin "1") (pinfunction "1_1") (pintype "passive"))
      (node (ref "JP85") (pin "1") (pinfunction "1_1") (pintype "passive"))
      (node (ref "R65") (pin "2") (pinfunction "2_2") (pintype "passive"))
      (node (ref "R66") (pin "2") (pinfunction "2_2") (pintype "passive"))
    )
    (net (code "23") (name "G18") (class "Default")
      (node (ref "J2") (pin "9") (pinfunction "9_9") (pintype "passive"))
      (node (ref "J3") (pin "9") (pinfunction "9_9") (pintype "passive"))
      (node (ref "JP106") (pin "1") (pinfunction "1_1") (pintype "passive"))
      (node (ref "JP68") (pin "1") (pinfunction "1_1") (pintype "passive"))
      (node (ref "JP87") (pin "1") (pinfunction "1_1") (pintype "passive"))
      (node (ref "R77") (pin "2") (pinfunction "2_2") (pintype "passive"))
      (node (ref "R78") (pin "2") (pinfunction "2_2") (pintype "passive"))
    )
    (net (code "24") (name "G19") (class "Default")
      (node (ref "J2") (pin "10") (pinfunction "10_10") (pintype "passive"))
      (node (ref "J3") (pin "10") (pinfunction "10_10") (pintype "passive"))
      (node (ref "JP107") (pin "1") (pinfunction "1_1") (pintype "passive"))
      (node (ref "JP69") (pin "1") (pinfunction "1_1") (pintype "passive"))
      (node (ref "JP88") (pin "1") (pinfunction "1_1") (pintype "passive"))
      (node (ref "R89") (pin "2") (pinfunction "2_2") (pintype "passive"))
      (node (ref "R90") (pin "2") (pinfunction "2_2") (pintype "passive"))
    )
    (net (code "25") (name "G23") (class "Default")
      (node (ref "JP113") (pin "1") (pinfunction "1_1") (pintype "passive"))
      (node (ref "JP75") (pin "1") (pinfunction "1_1") (pintype "passive"))
      (node (ref "JP94") (pin "1") (pinfunction "1_1") (pintype "passive"))
    )
    (net (code "26") (name "G25") (class "Default")
      (node (ref "JP28") (pin "1") (pinfunction "1_1") (pintype "passive"))
      (node (ref "JP47") (pin "1") (pinfunction "1_1") (pintype "passive"))
      (node (ref "JP9") (pin "1") (pinfunction "1_1") (pintype "passive"))
      (node (ref "R38") (pin "1") (pinfunction "1_1") (pintype "passive"))
      (node (ref "S2") (pin "3") (pinfunction "2_3") (pintype "passive"))
      (node (ref "S2") (pin "4") (pinfunction "2_4") (pintype "passive"))
    )
    (net (code "27") (name "G26") (class "Default")
      (node (ref "J2") (pin "11") (pinfunction "11_11") (pintype "passive"))
      (node (ref "J3") (pin "11") (pinfunction "11_11") (pintype "passive"))
      (node (ref "JP10") (pin "1") (pinfunction "1_1") (pintype "passive"))
      (node (ref "JP29") (pin "1") (pinfunction "1_1") (pintype "passive"))
      (node (ref "JP48") (pin "1") (pinfunction "1_1") (pintype "passive"))
      (node (ref "R93") (pin "2") (pinfunction "2_2") (pintype "passive"))
      (node (ref "R98") (pin "2") (pinfunction "2_2") (pintype "passive"))
    )
    (net (code "28") (name "G27") (class "Default")
      (node (ref "J2") (pin "12") (pinfunction "12_12") (pintype "passive"))
      (node (ref "J3") (pin "12") (pinfunction "12_12") (pintype "passive"))
      (node (ref "JP11") (pin "1") (pinfunction "1_1") (pintype "passive"))
      (node (ref "JP30") (pin "1") (pinfunction "1_1") (pintype "passive"))
      (node (ref "JP49") (pin "1") (pinfunction "1_1") (pintype "passive"))
      (node (ref "R103") (pin "2") (pinfunction "2_2") (pintype "passive"))
      (node (ref "R108") (pin "2") (pinfunction "2_2") (pintype "passive"))
    )
    (net (code "29") (name "G32") (class "Default")
      (node (ref "C2") (pin "1") (pinfunction "1_1") (pintype "passive"))
      (node (ref "JP26") (pin "1") (pinfunction "1_1") (pintype "passive"))
      (node (ref "JP45") (pin "1") (pinfunction "1_1") (pintype "passive"))
      (node (ref "JP7") (pin "1") (pinfunction "1_1") (pintype "passive"))
      (node (ref "R113") (pin "1") (pinfunction "1_1") (pintype "passive"))
    )
    (net (code "30") (name "G33") (class "Default")
      (node (ref "C27") (pin "1") (pinfunction "1_1") (pintype "passive"))
      (node (ref "JP27") (pin "1") (pinfunction "1_1") (pintype "passive"))
      (node (ref "JP46") (pin "1") (pinfunction "1_1") (pintype "passive"))
      (node (ref "JP8") (pin "1") (pinfunction "1_1") (pintype "passive"))
      (node (ref "R114") (pin "2") (pinfunction "2_2") (pintype "passive"))
    )
    (net (code "31") (name "G34") (class "Default")
      (node (ref "JP24") (pin "1") (pinfunction "1_1") (pintype "passive"))
      (node (ref "JP43") (pin "1") (pinfunction "1_1") (pintype "passive"))
      (node (ref "JP5") (pin "1") (pinfunction "1_1") (pintype "passive"))
      (node (ref "R1") (pin "1") (pinfunction "1_1") (pintype "passive"))
      (node (ref "U1") (pin "20") (pinfunction "ALERT_20") (pintype "bidirectional"))
    )
    (net (code "32") (name "G35") (class "Default")
      (node (ref "JP25") (pin "1") (pinfunction "1_1") (pintype "passive"))
      (node (ref "JP44") (pin "1") (pinfunction "1_1") (pintype "passive"))
      (node (ref "JP6") (pin "1") (pinfunction "1_1") (pintype "passive"))
    )
    (net (code "33") (name "GND") (class "Default")
      (node (ref "C10") (pin "1") (pinfunction "1_1") (pintype "passive"))
      (node (ref "C17") (pin "2") (pinfunction "2_2") (pintype "passive"))
      (node (ref "C18") (pin "1") (pinfunction "1_1") (pintype "passive"))
      (node (ref "C19") (pin "1") (pinfunction "1_1") (pintype "passive"))
      (node (ref "C2") (pin "2") (pinfunction "2_2") (pintype "passive"))
      (node (ref "C21") (pin "2") (pinfunction "2_2") (pintype "passive"))
      (node (ref "C22") (pin "2") (pinfunction "2_2") (pintype "passive"))
      (node (ref "C23") (pin "2") (pinfunction "2_2") (pintype "passive"))
      (node (ref "C24") (pin "2") (pinfunction "2_2") (pintype "passive"))
      (node (ref "C25") (pin "2") (pinfunction "2_2") (pintype "passive"))
      (node (ref "C27") (pin "2") (pinfunction "2_2") (pintype "passive"))
      (node (ref "C28") (pin "2") (pinfunction "2_2") (pintype "passive"))
      (node (ref "C29") (pin "2") (pinfunction "2_2") (pintype "passive"))
      (node (ref "C30") (pin "2") (pinfunction "2_2") (pintype "passive"))
      (node (ref "C5") (pin "1") (pinfunction "1_1") (pintype "passive"))
      (node (ref "C53") (pin "1") (pinfunction "1_1") (pintype "passive"))
      (node (ref "C59") (pin "1") (pinfunction "1_1") (pintype "passive"))
      (node (ref "C8") (pin "2") (pinfunction "2_2") (pintype "passive"))
      (node (ref "CON1") (pin "-") (pinfunction "-_-") (pintype "power_in"))
      (node (ref "IC1") (pin "2") (pinfunction "K_2") (pintype "bidirectional"))
      (node (ref "IC10") (pin "2") (pinfunction "K_2") (pintype "bidirectional"))
      (node (ref "IC11") (pin "2") (pinfunction "K_2") (pintype "bidirectional"))
      (node (ref "IC11") (pin "3") (pinfunction "E_3") (pintype "bidirectional"))
      (node (ref "IC12") (pin "2") (pinfunction "K_2") (pintype "bidirectional"))
      (node (ref "IC13") (pin "2") (pinfunction "K_2") (pintype "bidirectional"))
      (node (ref "IC14") (pin "2") (pinfunction "K_2") (pintype "bidirectional"))
      (node (ref "IC15") (pin "2") (pinfunction "K_2") (pintype "bidirectional"))
      (node (ref "IC16") (pin "2") (pinfunction "K_2") (pintype "bidirectional"))
      (node (ref "IC17") (pin "2") (pinfunction "K_2") (pintype "bidirectional"))
      (node (ref "IC18") (pin "2") (pinfunction "K_2") (pintype "bidirectional"))
      (node (ref "IC19") (pin "2") (pinfunction "K_2") (pintype "bidirectional"))
      (node (ref "IC2") (pin "2") (pinfunction "K_2") (pintype "bidirectional"))
      (node (ref "IC20") (pin "2") (pinfunction "K_2") (pintype "bidirectional"))
      (node (ref "IC21") (pin "3") (pinfunction "CATHODE_3") (pintype "bidirectional"))
      (node (ref "IC22") (pin "3") (pinfunction "CATHODE_3") (pintype "bidirectional"))
      (node (ref "IC23") (pin "3") (pinfunction "CATHODE_3") (pintype "bidirectional"))
      (node (ref "IC24") (pin "3") (pinfunction "CATHODE_3") (pintype "bidirectional"))
      (node (ref "IC25") (pin "5") (pinfunction "GND_5") (pintype "bidirectional"))
      (node (ref "IC26") (pin "5") (pinfunction "GND_5") (pintype "bidirectional"))
      (node (ref "IC27") (pin "1") (pinfunction "GROUND_1") (pintype "bidirectional"))
      (node (ref "IC3") (pin "2") (pinfunction "K_2") (pintype "bidirectional"))
      (node (ref "IC4") (pin "2") (pinfunction "K_2") (pintype "bidirectional"))
      (node (ref "IC5") (pin "2") (pinfunction "K_2") (pintype "bidirectional"))
      (node (ref "IC6") (pin "2") (pinfunction "K_2") (pintype "bidirectional"))
      (node (ref "IC6") (pin "3") (pinfunction "E_3") (pintype "bidirectional"))
      (node (ref "IC7") (pin "2") (pinfunction "K_2") (pintype "bidirectional"))
      (node (ref "IC8") (pin "2") (pinfunction "K_2") (pintype "bidirectional"))
      (node (ref "IC8") (pin "3") (pinfunction "E_3") (pintype "bidirectional"))
      (node (ref "IC9") (pin "2") (pinfunction "K_2") (pintype "bidirectional"))
      (node (ref "IC9") (pin "3") (pinfunction "E_3") (pintype "bidirectional"))
      (node (ref "J1") (pin "1") (pinfunction "S_1") (pintype "passive"))
      (node (ref "J4") (pin "1") (pinfunction "1_1") (pintype "passive"))
      (node (ref "J5") (pin "1") (pinfunction "1_1") (pintype "passive"))
      (node (ref "J8") (pin "1") (pinfunction "1_1") (pintype "passive"))
      (node (ref "JP108") (pin "1") (pinfunction "1_1") (pintype "passive"))
      (node (ref "JP114") (pin "1") (pinfunction "1_1") (pintype "passive"))
      (node (ref "JP116") (pin "P$1") (pinfunction "1_P$1") (pintype "passive"))
      (node (ref "JP118") (pin "P$1") (pinfunction "1_P$1") (pintype "passive"))
      (node (ref "JP120") (pin "P$1") (pinfunction "1_P$1") (pintype "passive"))
      (node (ref "JP122") (pin "P$1") (pinfunction "1_P$1") (pintype "passive"))
      (node (ref "JP125") (pin "1") (pinfunction "1_1") (pintype "passive"))
      (node (ref "JP130") (pin "1") (pinfunction "1_1") (pintype "passive"))
      (node (ref "JP131") (pin "1") (pinfunction "1_1") (pintype "passive"))
      (node (ref "JP132") (pin "1") (pinfunction "1_1") (pintype "passive"))
      (node (ref "JP135") (pin "P$1") (pinfunction "1_P$1") (pintype "passive"))
      (node (ref "JP136") (pin "P$1") (pinfunction "1_P$1") (pintype "passive"))
      (node (ref "JP14") (pin "1") (pinfunction "1_1") (pintype "passive"))
      (node (ref "JP33") (pin "1") (pinfunction "1_1") (pintype "passive"))
      (node (ref "JP52") (pin "1") (pinfunction "1_1") (pintype "passive"))
      (node (ref "JP70") (pin "1") (pinfunction "1_1") (pintype "passive"))
      (node (ref "JP76") (pin "1") (pinfunction "1_1") (pintype "passive"))
      (node (ref "JP89") (pin "1") (pinfunction "1_1") (pintype "passive"))
      (node (ref "JP95") (pin "1") (pinfunction "1_1") (pintype "passive"))
      (node (ref "PS1") (pin "2") (pinfunction "GND_2") (pintype "bidirectional"))
      (node (ref "PS2") (pin "2") (pinfunction "GND_2") (pintype "bidirectional"))
      (node (ref "PS7") (pin "2") (pinfunction "GND_2") (pintype "bidirectional"))
      (node (ref "PS8") (pin "2") (pinfunction "GND_2") (pintype "bidirectional"))
      (node (ref "Q41") (pin "D") (pinfunction "D_D") (pintype "passive"))
      (node (ref "Q43") (pin "D") (pinfunction "D_D") (pintype "passive"))
      (node (ref "Q5") (pin "2") (pinfunction "S_2") (pintype "bidirectional"))
      (node (ref "Q8") (pin "1") (pinfunction "G_1") (pintype "bidirectional"))
      (node (ref "R1") (pin "2") (pinfunction "2_2") (pintype "passive"))
      (node (ref "R15") (pin "1") (pinfunction "1_1") (pintype "passive"))
      (node (ref "R31") (pin "1") (pinfunction "1_1") (pintype "passive"))
      (node (ref "R32") (pin "1") (pinfunction "1_1") (pintype "passive"))
      (node (ref "U1") (pin "3") (pinfunction "VSS_3") (pintype "passive"))
    )
    (net (code "34") (name "IN+") (class "Default")
      (node (ref "C7") (pin "1") (pinfunction "1_1") (pintype "passive"))
      (node (ref "D8") (pin "1") (pinfunction "K_1") (pintype "bidirectional"))
      (node (ref "Q13") (pin "D") (pinfunction "D_D") (pintype "passive"))
      (node (ref "Q21") (pin "D") (pinfunction "D_D") (pintype "passive"))
      (node (ref "Q29") (pin "D") (pinfunction "D_D") (pintype "passive"))
      (node (ref "Q35") (pin "D") (pinfunction "D_D") (pintype "passive"))
      (node (ref "Q46") (pin "D") (pinfunction "D_D") (pintype "passive"))
      (node (ref "Q49") (pin "D") (pinfunction "D_D") (pintype "passive"))
    )
    (net (code "35") (name "IN-") (class "Default")
      (node (ref "C26") (pin "1") (pinfunction "1_1") (pintype "passive"))
      (node (ref "D10") (pin "1") (pinfunction "K_1") (pintype "bidirectional"))
      (node (ref "JP141") (pin "P$1") (pinfunction "1_P$1") (pintype "passive"))
      (node (ref "Q14") (pin "D") (pinfunction "D_D") (pintype "passive"))
      (node (ref "Q22") (pin "D") (pinfunction "D_D") (pintype "passive"))
      (node (ref "Q30") (pin "D") (pinfunction "D_D") (pintype "passive"))
      (node (ref "Q38") (pin "D") (pinfunction "D_D") (pintype "passive"))
      (node (ref "Q42") (pin "D") (pinfunction "D_D") (pintype "passive"))
      (node (ref "Q52") (pin "D") (pinfunction "D_D") (pintype "passive"))
    )
    (net (code "36") (name "ISOIN") (class "Default")
      (node (ref "C10") (pin "2") (pinfunction "2_2") (pintype "passive"))
      (node (ref "C30") (pin "1") (pinfunction "1_1") (pintype "passive"))
      (node (ref "C5") (pin "2") (pinfunction "2_2") (pintype "passive"))
      (node (ref "C53") (pin "2") (pinfunction "2_2") (pintype "passive"))
      (node (ref "C59") (pin "2") (pinfunction "2_2") (pintype "passive"))
      (node (ref "IC27") (pin "3") (pinfunction "VIN_3") (pintype "bidirectional"))
      (node (ref "JP117") (pin "P$1") (pinfunction "1_P$1") (pintype "passive"))
      (node (ref "PS1") (pin "1") (pinfunction "VIN_1") (pintype "bidirectional"))
      (node (ref "PS2") (pin "1") (pinfunction "VIN_1") (pintype "bidirectional"))
      (node (ref "PS7") (pin "1") (pinfunction "VIN_1") (pintype "bidirectional"))
      (node (ref "PS8") (pin "1") (pinfunction "VIN_1") (pintype "bidirectional"))
    )
    (net (code "37") (name "LIN") (class "Default")
      (node (ref "C61") (pin "1") (pinfunction "1_1") (pintype "passive"))
      (node (ref "D21") (pin "1") (pinfunction "K_1") (pintype "bidirectional"))
      (node (ref "IC25") (pin "3") (pinfunction "IN-_1_3") (pintype "bidirectional"))
      (node (ref "IC25") (pin "4") (pinfunction "IN-_2_4") (pintype "bidirectional"))
      (node (ref "JP133") (pin "1") (pinfunction "1_1") (pintype "passive"))
      (node (ref "JP134") (pin "1") (pinfunction "1_1") (pintype "passive"))
      (node (ref "JP138") (pin "P$1") (pinfunction "1_P$1") (pintype "passive"))
      (node (ref "L2") (pin "1") (pinfunction "1_1") (pintype "passive"))
      (node (ref "Q55") (pin "D") (pinfunction "D_D") (pintype "passive"))
    )
    (net (code "38") (name "LOUT") (class "Default")
      (node (ref "C12") (pin "1") (pinfunction "1_1") (pintype "passive"))
      (node (ref "D9") (pin "1") (pinfunction "K_1") (pintype "bidirectional"))
      (node (ref "IC26") (pin "1") (pinfunction "IN+_1_1") (pintype "bidirectional"))
      (node (ref "IC26") (pin "2") (pinfunction "IN+_2_2") (pintype "bidirectional"))
      (node (ref "JP123") (pin "1") (pinfunction "1_1") (pintype "passive"))
      (node (ref "JP124") (pin "1") (pinfunction "1_1") (pintype "passive"))
      (node (ref "JP139") (pin "P$1") (pinfunction "1_P$1") (pintype "passive"))
      (node (ref "L2") (pin "2") (pinfunction "2_2") (pintype "passive"))
      (node (ref "Q56") (pin "D") (pinfunction "D_D") (pintype "passive"))
    )
    (net (code "39") (name "Net-(C6-Pad2)") (class "Default")
      (node (ref "C6") (pin "2") (pinfunction "2_2") (pintype "passive"))
      (node (ref "R96") (pin "1") (pinfunction "1_1") (pintype "passive"))
    )
    (net (code "40") (name "Net-(C7-Pad2)") (class "Default")
      (node (ref "C7") (pin "2") (pinfunction "2_2") (pintype "passive"))
      (node (ref "R97") (pin "2") (pinfunction "2_2") (pintype "passive"))
    )
    (net (code "41") (name "Net-(C12-Pad2)") (class "Default")
      (node (ref "C12") (pin "2") (pinfunction "2_2") (pintype "passive"))
      (node (ref "R101") (pin "1") (pinfunction "1_1") (pintype "passive"))
    )
    (net (code "42") (name "Net-(C26-Pad2)") (class "Default")
      (node (ref "C26") (pin "2") (pinfunction "2_2") (pintype "passive"))
      (node (ref "R102") (pin "2") (pinfunction "2_2") (pintype "passive"))
    )
    (net (code "43") (name "Net-(C55-Pad2)") (class "Default")
      (node (ref "C55") (pin "2") (pinfunction "2_2") (pintype "passive"))
      (node (ref "R106") (pin "1") (pinfunction "1_1") (pintype "passive"))
    )
    (net (code "44") (name "Net-(C56-Pad2)") (class "Default")
      (node (ref "C56") (pin "2") (pinfunction "2_2") (pintype "passive"))
      (node (ref "R107") (pin "2") (pinfunction "2_2") (pintype "passive"))
    )
    (net (code "45") (name "Net-(C61-Pad2)") (class "Default")
      (node (ref "C61") (pin "2") (pinfunction "2_2") (pintype "passive"))
      (node (ref "R111") (pin "1") (pinfunction "1_1") (pintype "passive"))
    )
    (net (code "46") (name "Net-(C62-Pad2)") (class "Default")
      (node (ref "C62") (pin "2") (pinfunction "2_2") (pintype "passive"))
      (node (ref "R112") (pin "2") (pinfunction "2_2") (pintype "passive"))
    )
    (net (code "47") (name "Net-(D1-A)") (class "Default")
      (node (ref "C3") (pin "2") (pinfunction "2_2") (pintype "passive"))
      (node (ref "C4") (pin "2") (pinfunction "2_2") (pintype "passive"))
      (node (ref "D1") (pin "2") (pinfunction "A_2") (pintype "bidirectional"))
      (node (ref "D8") (pin "2") (pinfunction "A_2") (pintype "bidirectional"))
      (node (ref "IC21") (pin "5") (pinfunction "GND_5") (pintype "bidirectional"))
      (node (ref "PS1") (pin "4") (pinfunction "0V_4") (pintype "bidirectional"))
      (node (ref "Q49") (pin "S") (pinfunction "S_S") (pintype "passive"))
      (node (ref "Q53") (pin "S") (pinfunction "S_S") (pintype "passive"))
      (node (ref "R95") (pin "1") (pinfunction "1_1") (pintype "passive"))
      (node (ref "R96") (pin "2") (pinfunction "2_2") (pintype "passive"))
      (node (ref "R97") (pin "1") (pinfunction "1_1") (pintype "passive"))
    )
    (net (code "48") (name "Net-(D2-PadA)") (class "Default")
      (node (ref "D2") (pin "A") (pinfunction "A_A") (pintype "passive"))
      (node (ref "R17") (pin "1") (pinfunction "1_1") (pintype "passive"))
    )
    (net (code "49") (name "Net-(D3-PadA)") (class "Default")
      (node (ref "D3") (pin "A") (pinfunction "A_A") (pintype "passive"))
      (node (ref "R20") (pin "1") (pinfunction "1_1") (pintype "passive"))
    )
    (net (code "50") (name "Net-(D4-PadA)") (class "Default")
      (node (ref "D4") (pin "A") (pinfunction "A_A") (pintype "passive"))
      (node (ref "R23") (pin "1") (pinfunction "1_1") (pintype "passive"))
    )
    (net (code "51") (name "Net-(D5-PadA)") (class "Default")
      (node (ref "D5") (pin "A") (pinfunction "A_A") (pintype "passive"))
      (node (ref "R26") (pin "1") (pinfunction "1_1") (pintype "passive"))
    )
    (net (code "52") (name "Net-(D6-PadA)") (class "Default")
      (node (ref "D6") (pin "A") (pinfunction "A_A") (pintype "passive"))
      (node (ref "R29") (pin "1") (pinfunction "1_1") (pintype "passive"))
    )
    (net (code "53") (name "Net-(D10-A)") (class "Default")
      (node (ref "C11") (pin "2") (pinfunction "2_2") (pintype "passive"))
      (node (ref "C9") (pin "2") (pinfunction "2_2") (pintype "passive"))
      (node (ref "D10") (pin "2") (pinfunction "A_2") (pintype "bidirectional"))
      (node (ref "D9") (pin "2") (pinfunction "A_2") (pintype "bidirectional"))
      (node (ref "IC22") (pin "5") (pinfunction "GND_5") (pintype "bidirectional"))
      (node (ref "PS2") (pin "4") (pinfunction "0V_4") (pintype "bidirectional"))
      (node (ref "Q52") (pin "S") (pinfunction "S_S") (pintype "passive"))
      (node (ref "Q56") (pin "S") (pinfunction "S_S") (pintype "passive"))
      (node (ref "R100") (pin "1") (pinfunction "1_1") (pintype "passive"))
      (node (ref "R101") (pin "2") (pinfunction "2_2") (pintype "passive"))
      (node (ref "R102") (pin "1") (pinfunction "1_1") (pintype "passive"))
    )
    (net (code "54") (name "Net-(D19-A)") (class "Default")
      (node (ref "C52") (pin "2") (pinfunction "2_2") (pintype "passive"))
      (node (ref "C54") (pin "2") (pinfunction "2_2") (pintype "passive"))
      (node (ref "D19") (pin "2") (pinfunction "A_2") (pintype "bidirectional"))
      (node (ref "D20") (pin "2") (pinfunction "A_2") (pintype "bidirectional"))
      (node (ref "IC23") (pin "5") (pinfunction "GND_5") (pintype "bidirectional"))
      (node (ref "PS7") (pin "4") (pinfunction "0V_4") (pintype "bidirectional"))
      (node (ref "Q50") (pin "S") (pinfunction "S_S") (pintype "passive"))
      (node (ref "Q54") (pin "S") (pinfunction "S_S") (pintype "passive"))
      (node (ref "R105") (pin "1") (pinfunction "1_1") (pintype "passive"))
      (node (ref "R106") (pin "2") (pinfunction "2_2") (pintype "passive"))
      (node (ref "R107") (pin "1") (pinfunction "1_1") (pintype "passive"))
    )
    (net (code "55") (name "Net-(D21-A)") (class "Default")
      (node (ref "C58") (pin "2") (pinfunction "2_2") (pintype "passive"))
      (node (ref "C60") (pin "2") (pinfunction "2_2") (pintype "passive"))
      (node (ref "D21") (pin "2") (pinfunction "A_2") (pintype "bidirectional"))
      (node (ref "D22") (pin "2") (pinfunction "A_2") (pintype "bidirectional"))
      (node (ref "IC24") (pin "5") (pinfunction "GND_5") (pintype "bidirectional"))
      (node (ref "PS8") (pin "4") (pinfunction "0V_4") (pintype "bidirectional"))
      (node (ref "Q51") (pin "S") (pinfunction "S_S") (pintype "passive"))
      (node (ref "Q55") (pin "S") (pinfunction "S_S") (pintype "passive"))
      (node (ref "R110") (pin "1") (pinfunction "1_1") (pintype "passive"))
      (node (ref "R111") (pin "2") (pinfunction "2_2") (pintype "passive"))
      (node (ref "R112") (pin "1") (pinfunction "1_1") (pintype "passive"))
    )
    (net (code "56") (name "Net-(IC1-A)") (class "Default")
      (node (ref "IC1") (pin "1") (pinfunction "A_1") (pintype "bidirectional"))
      (node (ref "R41") (pin "1") (pinfunction "1_1") (pintype "passive"))
    )
    (net (code "57") (name "Net-(IC2-A)") (class "Default")
      (node (ref "IC2") (pin "1") (pinfunction "A_1") (pintype "bidirectional"))
      (node (ref "R42") (pin "1") (pinfunction "1_1") (pintype "passive"))
    )
    (net (code "58") (name "Net-(IC3-A)") (class "Default")
      (node (ref "IC3") (pin "1") (pinfunction "A_1") (pintype "bidirectional"))
      (node (ref "R43") (pin "1") (pinfunction "1_1") (pintype "passive"))
    )
    (net (code "59") (name "Net-(IC4-A)") (class "Default")
      (node (ref "IC4") (pin "1") (pinfunction "A_1") (pintype "bidirectional"))
      (node (ref "R44") (pin "1") (pinfunction "1_1") (pintype "passive"))
    )
    (net (code "60") (name "Net-(IC5-A)") (class "Default")
      (node (ref "IC5") (pin "1") (pinfunction "A_1") (pintype "bidirectional"))
      (node (ref "R53") (pin "1") (pinfunction "1_1") (pintype "passive"))
    )
    (net (code "61") (name "Net-(IC6-A)") (class "Default")
      (node (ref "IC6") (pin "1") (pinfunction "A_1") (pintype "bidirectional"))
      (node (ref "R54") (pin "1") (pinfunction "1_1") (pintype "passive"))
    )
    (net (code "62") (name "Net-(IC7-A)") (class "Default")
      (node (ref "IC7") (pin "1") (pinfunction "A_1") (pintype "bidirectional"))
      (node (ref "R55") (pin "1") (pinfunction "1_1") (pintype "passive"))
    )
    (net (code "63") (name "Net-(IC8-A)") (class "Default")
      (node (ref "IC8") (pin "1") (pinfunction "A_1") (pintype "bidirectional"))
      (node (ref "R56") (pin "1") (pinfunction "1_1") (pintype "passive"))
    )
    (net (code "64") (name "Net-(IC9-A)") (class "Default")
      (node (ref "IC9") (pin "1") (pinfunction "A_1") (pintype "bidirectional"))
      (node (ref "R65") (pin "1") (pinfunction "1_1") (pintype "passive"))
    )
    (net (code "65") (name "Net-(IC10-A)") (class "Default")
      (node (ref "IC10") (pin "1") (pinfunction "A_1") (pintype "bidirectional"))
      (node (ref "R66") (pin "1") (pinfunction "1_1") (pintype "passive"))
    )
    (net (code "66") (name "Net-(IC11-A)") (class "Default")
      (node (ref "IC11") (pin "1") (pinfunction "A_1") (pintype "bidirectional"))
      (node (ref "R67") (pin "1") (pinfunction "1_1") (pintype "passive"))
    )
    (net (code "67") (name "Net-(IC12-A)") (class "Default")
      (node (ref "IC12") (pin "1") (pinfunction "A_1") (pintype "bidirectional"))
      (node (ref "R68") (pin "1") (pinfunction "1_1") (pintype "passive"))
    )
    (net (code "68") (name "Net-(IC13-A)") (class "Default")
      (node (ref "IC13") (pin "1") (pinfunction "A_1") (pintype "bidirectional"))
      (node (ref "R77") (pin "1") (pinfunction "1_1") (pintype "passive"))
    )
    (net (code "69") (name "Net-(IC14-A)") (class "Default")
      (node (ref "IC14") (pin "1") (pinfunction "A_1") (pintype "bidirectional"))
      (node (ref "R78") (pin "1") (pinfunction "1_1") (pintype "passive"))
    )
    (net (code "70") (name "Net-(IC15-A)") (class "Default")
      (node (ref "IC15") (pin "1") (pinfunction "A_1") (pintype "bidirectional"))
      (node (ref "R79") (pin "1") (pinfunction "1_1") (pintype "passive"))
    )
    (net (code "71") (name "Net-(IC16-A)") (class "Default")
      (node (ref "IC16") (pin "1") (pinfunction "A_1") (pintype "bidirectional"))
      (node (ref "R80") (pin "1") (pinfunction "1_1") (pintype "passive"))
    )
    (net (code "72") (name "Net-(IC17-A)") (class "Default")
      (node (ref "IC17") (pin "1") (pinfunction "A_1") (pintype "bidirectional"))
      (node (ref "R89") (pin "1") (pinfunction "1_1") (pintype "passive"))
    )
    (net (code "73") (name "Net-(IC18-A)") (class "Default")
      (node (ref "IC18") (pin "1") (pinfunction "A_1") (pintype "bidirectional"))
      (node (ref "R90") (pin "1") (pinfunction "1_1") (pintype "passive"))
    )
    (net (code "74") (name "Net-(IC19-A)") (class "Default")
      (node (ref "IC19") (pin "1") (pinfunction "A_1") (pintype "bidirectional"))
      (node (ref "R91") (pin "1") (pinfunction "1_1") (pintype "passive"))
    )
    (net (code "75") (name "Net-(IC20-A)") (class "Default")
      (node (ref "IC20") (pin "1") (pinfunction "A_1") (pintype "bidirectional"))
      (node (ref "R92") (pin "1") (pinfunction "1_1") (pintype "passive"))
    )
    (net (code "76") (name "Net-(IC21-ANODE)") (class "Default")
      (node (ref "IC21") (pin "2") (pinfunction "ANODE_2") (pintype "bidirectional"))
      (node (ref "R93") (pin "1") (pinfunction "1_1") (pintype "passive"))
    )
    (net (code "77") (name "Net-(IC21-VCC)") (class "Default")
      (node (ref "C3") (pin "1") (pinfunction "1_1") (pintype "passive"))
      (node (ref "C4") (pin "1") (pinfunction "1_1") (pintype "passive"))
      (node (ref "IC21") (pin "8") (pinfunction "VCC_8") (pintype "bidirectional"))
      (node (ref "PS1") (pin "6") (pinfunction "+VO_6") (pintype "bidirectional"))
    )
    (net (code "78") (name "Net-(IC21-VO_(OUTPUT))") (class "Default")
      (node (ref "IC21") (pin "6") (pinfunction "VO_(OUTPUT)_6") (pintype "bidirectional"))
      (node (ref "R94") (pin "2") (pinfunction "2_2") (pintype "passive"))
    )
    (net (code "79") (name "Net-(IC22-ANODE)") (class "Default")
      (node (ref "IC22") (pin "2") (pinfunction "ANODE_2") (pintype "bidirectional"))
      (node (ref "R98") (pin "1") (pinfunction "1_1") (pintype "passive"))
    )
    (net (code "80") (name "Net-(IC22-VCC)") (class "Default")
      (node (ref "C11") (pin "1") (pinfunction "1_1") (pintype "passive"))
      (node (ref "C9") (pin "1") (pinfunction "1_1") (pintype "passive"))
      (node (ref "IC22") (pin "8") (pinfunction "VCC_8") (pintype "bidirectional"))
      (node (ref "PS2") (pin "6") (pinfunction "+VO_6") (pintype "bidirectional"))
    )
    (net (code "81") (name "Net-(IC22-VO_(OUTPUT))") (class "Default")
      (node (ref "IC22") (pin "6") (pinfunction "VO_(OUTPUT)_6") (pintype "bidirectional"))
      (node (ref "R99") (pin "2") (pinfunction "2_2") (pintype "passive"))
    )
    (net (code "82") (name "Net-(IC23-ANODE)") (class "Default")
      (node (ref "IC23") (pin "2") (pinfunction "ANODE_2") (pintype "bidirectional"))
      (node (ref "R103") (pin "1") (pinfunction "1_1") (pintype "passive"))
    )
    (net (code "83") (name "Net-(IC23-VCC)") (class "Default")
      (node (ref "C52") (pin "1") (pinfunction "1_1") (pintype "passive"))
      (node (ref "C54") (pin "1") (pinfunction "1_1") (pintype "passive"))
      (node (ref "IC23") (pin "8") (pinfunction "VCC_8") (pintype "bidirectional"))
      (node (ref "PS7") (pin "6") (pinfunction "+VO_6") (pintype "bidirectional"))
    )
    (net (code "84") (name "Net-(IC23-VO_(OUTPUT))") (class "Default")
      (node (ref "IC23") (pin "6") (pinfunction "VO_(OUTPUT)_6") (pintype "bidirectional"))
      (node (ref "R104") (pin "2") (pinfunction "2_2") (pintype "passive"))
    )
    (net (code "85") (name "Net-(IC24-ANODE)") (class "Default")
      (node (ref "IC24") (pin "2") (pinfunction "ANODE_2") (pintype "bidirectional"))
      (node (ref "R108") (pin "1") (pinfunction "1_1") (pintype "passive"))
    )
    (net (code "86") (name "Net-(IC24-VCC)") (class "Default")
      (node (ref "C58") (pin "1") (pinfunction "1_1") (pintype "passive"))
      (node (ref "C60") (pin "1") (pinfunction "1_1") (pintype "passive"))
      (node (ref "IC24") (pin "8") (pinfunction "VCC_8") (pintype "bidirectional"))
      (node (ref "PS8") (pin "6") (pinfunction "+VO_6") (pintype "bidirectional"))
    )
    (net (code "87") (name "Net-(IC24-VO_(OUTPUT))") (class "Default")
      (node (ref "IC24") (pin "6") (pinfunction "VO_(OUTPUT)_6") (pintype "bidirectional"))
      (node (ref "R109") (pin "2") (pinfunction "2_2") (pintype "passive"))
    )
    (net (code "88") (name "Net-(IC25-VOUT)") (class "Default")
      (node (ref "IC25") (pin "7") (pinfunction "VOUT_7") (pintype "bidirectional"))
      (node (ref "JP129") (pin "1") (pinfunction "1_1") (pintype "passive"))
      (node (ref "R113") (pin "2") (pinfunction "2_2") (pintype "passive"))
    )
    (net (code "89") (name "Net-(IC26-VOUT)") (class "Default")
      (node (ref "IC26") (pin "7") (pinfunction "VOUT_7") (pintype "bidirectional"))
      (node (ref "JP127") (pin "1") (pinfunction "1_1") (pintype "passive"))
      (node (ref "R114") (pin "1") (pinfunction "1_1") (pintype "passive"))
    )
    (net (code "90") (name "Net-(J1B-S)") (class "Default")
      (node (ref "J1") (pin "2") (pinfunction "S_2") (pintype "passive"))
      (node (ref "R38") (pin "2") (pinfunction "2_2") (pintype "passive"))
      (node (ref "U1") (pin "6") (pinfunction "TS1_6") (pintype "input"))
    )
    (net (code "91") (name "Net-(JP19-Pad1)") (class "Default")
      (node (ref "JP19") (pin "1") (pinfunction "1_1") (pintype "passive"))
      (node (ref "JP38") (pin "1") (pinfunction "1_1") (pintype "passive"))
      (node (ref "JP57") (pin "1") (pinfunction "1_1") (pintype "passive"))
      (node (ref "SW1") (pin "2") (pinfunction "2_2") (pintype "passive"))
    )
    (net (code "92") (name "Net-(Q1-D)") (class "Default")
      (node (ref "D2") (pin "C") (pinfunction "C_C") (pintype "passive"))
      (node (ref "Q1") (pin "3") (pinfunction "D_3") (pintype "bidirectional"))
      (node (ref "R16") (pin "1") (pinfunction "1_1") (pintype "passive"))
    )
    (net (code "93") (name "Net-(Q1-G)") (class "Default")
      (node (ref "Q1") (pin "1") (pinfunction "G_1") (pintype "bidirectional"))
      (node (ref "R18") (pin "1") (pinfunction "1_1") (pintype "passive"))
    )
    (net (code "94") (name "Net-(Q2-D)") (class "Default")
      (node (ref "D3") (pin "C") (pinfunction "C_C") (pintype "passive"))
      (node (ref "Q2") (pin "3") (pinfunction "D_3") (pintype "bidirectional"))
      (node (ref "R19") (pin "1") (pinfunction "1_1") (pintype "passive"))
    )
    (net (code "95") (name "Net-(Q2-G)") (class "Default")
      (node (ref "Q2") (pin "1") (pinfunction "G_1") (pintype "bidirectional"))
      (node (ref "R21") (pin "1") (pinfunction "1_1") (pintype "passive"))
    )
    (net (code "96") (name "Net-(Q3-D)") (class "Default")
      (node (ref "D4") (pin "C") (pinfunction "C_C") (pintype "passive"))
      (node (ref "Q3") (pin "3") (pinfunction "D_3") (pintype "bidirectional"))
      (node (ref "R22") (pin "1") (pinfunction "1_1") (pintype "passive"))
    )
    (net (code "97") (name "Net-(Q3-G)") (class "Default")
      (node (ref "Q3") (pin "1") (pinfunction "G_1") (pintype "bidirectional"))
      (node (ref "R24") (pin "1") (pinfunction "1_1") (pintype "passive"))
    )
    (net (code "98") (name "Net-(Q4-D)") (class "Default")
      (node (ref "D5") (pin "C") (pinfunction "C_C") (pintype "passive"))
      (node (ref "Q4") (pin "3") (pinfunction "D_3") (pintype "bidirectional"))
      (node (ref "R25") (pin "1") (pinfunction "1_1") (pintype "passive"))
    )
    (net (code "99") (name "Net-(Q4-G)") (class "Default")
      (node (ref "Q4") (pin "1") (pinfunction "G_1") (pintype "bidirectional"))
      (node (ref "R27") (pin "1") (pinfunction "1_1") (pintype "passive"))
    )
    (net (code "100") (name "Net-(Q5-D)") (class "Default")
      (node (ref "D6") (pin "C") (pinfunction "C_C") (pintype "passive"))
      (node (ref "Q5") (pin "3") (pinfunction "D_3") (pintype "bidirectional"))
      (node (ref "R28") (pin "1") (pinfunction "1_1") (pintype "passive"))
    )
    (net (code "101") (name "Net-(Q5-G)") (class "Default")
      (node (ref "Q5") (pin "1") (pinfunction "G_1") (pintype "bidirectional"))
      (node (ref "R30") (pin "1") (pinfunction "1_1") (pintype "passive"))
    )
    (net (code "102") (name "Net-(Q6-PadG)") (class "Default")
      (node (ref "Q6") (pin "G") (pinfunction "G_G") (pintype "passive"))
      (node (ref "Q7") (pin "G") (pinfunction "G_G") (pintype "passive"))
      (node (ref "R2") (pin "1") (pinfunction "1_1") (pintype "passive"))
      (node (ref "R3") (pin "2") (pinfunction "2_2") (pintype "passive"))
    )
    (net (code "103") (name "Net-(Q6-PadS)") (class "Default")
      (node (ref "Q6") (pin "S") (pinfunction "S_S") (pintype "passive"))
      (node (ref "Q7") (pin "S") (pinfunction "S_S") (pintype "passive"))
      (node (ref "R2") (pin "2") (pinfunction "2_2") (pintype "passive"))
    )
    (net (code "104") (name "Net-(Q8-D)") (class "Default")
      (node (ref "D7") (pin "A") (pinfunction "A_A") (pintype "passive"))
      (node (ref "Q8") (pin "3") (pinfunction "D_3") (pintype "bidirectional"))
      (node (ref "R36") (pin "1") (pinfunction "1_1") (pintype "passive"))
    )
    (net (code "105") (name "Net-(Q9-S)") (class "Default")
      (node (ref "Q9") (pin "3") (pinfunction "S_3") (pintype "passive"))
      (node (ref "R32") (pin "2") (pinfunction "2_2") (pintype "passive"))
      (node (ref "R33") (pin "1") (pinfunction "1_1") (pintype "passive"))
      (node (ref "R34") (pin "2") (pinfunction "2_2") (pintype "passive"))
    )
    (net (code "106") (name "Net-(Q10-D)") (class "Default")
      (node (ref "Q10") (pin "2") (pinfunction "D_2") (pintype "passive"))
      (node (ref "Q9") (pin "2") (pinfunction "D_2") (pintype "passive"))
    )
    (net (code "107") (name "Net-(Q10-G)") (class "Default")
      (node (ref "D7") (pin "C") (pinfunction "C_C") (pintype "passive"))
      (node (ref "Q10") (pin "1") (pinfunction "G_1") (pintype "passive"))
      (node (ref "R35") (pin "1") (pinfunction "1_1") (pintype "passive"))
      (node (ref "R36") (pin "2") (pinfunction "2_2") (pintype "passive"))
    )
    (net (code "108") (name "Net-(Q11-PadG)") (class "Default")
      (node (ref "Q11") (pin "G") (pinfunction "G_G") (pintype "passive"))
      (node (ref "Q30") (pin "G") (pinfunction "G_G") (pintype "passive"))
      (node (ref "R61") (pin "1") (pinfunction "1_1") (pintype "passive"))
      (node (ref "R62") (pin "2") (pinfunction "2_2") (pintype "passive"))
    )
    (net (code "109") (name "Net-(Q11-PadS)") (class "Default")
      (node (ref "Q11") (pin "S") (pinfunction "S_S") (pintype "passive"))
      (node (ref "Q30") (pin "S") (pinfunction "S_S") (pintype "passive"))
      (node (ref "R61") (pin "2") (pinfunction "2_2") (pintype "passive"))
    )
    (net (code "110") (name "Net-(Q12-PadG)") (class "Default")
      (node (ref "Q12") (pin "G") (pinfunction "G_G") (pintype "passive"))
      (node (ref "Q13") (pin "G") (pinfunction "G_G") (pintype "passive"))
      (node (ref "R4") (pin "1") (pinfunction "1_1") (pintype "passive"))
      (node (ref "R5") (pin "2") (pinfunction "2_2") (pintype "passive"))
    )
    (net (code "111") (name "Net-(Q12-PadS)") (class "Default")
      (node (ref "Q12") (pin "S") (pinfunction "S_S") (pintype "passive"))
      (node (ref "Q13") (pin "S") (pinfunction "S_S") (pintype "passive"))
      (node (ref "R4") (pin "2") (pinfunction "2_2") (pintype "passive"))
    )
    (net (code "112") (name "Net-(Q14-PadG)") (class "Default")
      (node (ref "Q14") (pin "G") (pinfunction "G_G") (pintype "passive"))
      (node (ref "Q15") (pin "G") (pinfunction "G_G") (pintype "passive"))
      (node (ref "R6") (pin "1") (pinfunction "1_1") (pintype "passive"))
      (node (ref "R7") (pin "2") (pinfunction "2_2") (pintype "passive"))
    )
    (net (code "113") (name "Net-(Q14-PadS)") (class "Default")
      (node (ref "Q14") (pin "S") (pinfunction "S_S") (pintype "passive"))
      (node (ref "Q15") (pin "S") (pinfunction "S_S") (pintype "passive"))
      (node (ref "R6") (pin "2") (pinfunction "2_2") (pintype "passive"))
    )
    (net (code "114") (name "Net-(Q16-PadG)") (class "Default")
      (node (ref "Q16") (pin "G") (pinfunction "G_G") (pintype "passive"))
      (node (ref "Q17") (pin "G") (pinfunction "G_G") (pintype "passive"))
      (node (ref "R39") (pin "1") (pinfunction "1_1") (pintype "passive"))
      (node (ref "R40") (pin "2") (pinfunction "2_2") (pintype "passive"))
    )
    (net (code "115") (name "Net-(Q16-PadS)") (class "Default")
      (node (ref "Q16") (pin "S") (pinfunction "S_S") (pintype "passive"))
      (node (ref "Q17") (pin "S") (pinfunction "S_S") (pintype "passive"))
      (node (ref "R39") (pin "2") (pinfunction "2_2") (pintype "passive"))
    )
    (net (code "116") (name "Net-(Q18-PadG)") (class "Default")
      (node (ref "Q18") (pin "G") (pinfunction "G_G") (pintype "passive"))
      (node (ref "Q19") (pin "G") (pinfunction "G_G") (pintype "passive"))
      (node (ref "R45") (pin "1") (pinfunction "1_1") (pintype "passive"))
      (node (ref "R46") (pin "2") (pinfunction "2_2") (pintype "passive"))
    )
    (net (code "117") (name "Net-(Q18-PadS)") (class "Default")
      (node (ref "Q18") (pin "S") (pinfunction "S_S") (pintype "passive"))
      (node (ref "Q19") (pin "S") (pinfunction "S_S") (pintype "passive"))
      (node (ref "R45") (pin "2") (pinfunction "2_2") (pintype "passive"))
    )
    (net (code "118") (name "Net-(Q20-PadG)") (class "Default")
      (node (ref "Q20") (pin "G") (pinfunction "G_G") (pintype "passive"))
      (node (ref "Q21") (pin "G") (pinfunction "G_G") (pintype "passive"))
      (node (ref "R47") (pin "1") (pinfunction "1_1") (pintype "passive"))
      (node (ref "R48") (pin "2") (pinfunction "2_2") (pintype "passive"))
    )
    (net (code "119") (name "Net-(Q20-PadS)") (class "Default")
      (node (ref "Q20") (pin "S") (pinfunction "S_S") (pintype "passive"))
      (node (ref "Q21") (pin "S") (pinfunction "S_S") (pintype "passive"))
      (node (ref "R47") (pin "2") (pinfunction "2_2") (pintype "passive"))
    )
    (net (code "120") (name "Net-(Q22-PadG)") (class "Default")
      (node (ref "Q22") (pin "G") (pinfunction "G_G") (pintype "passive"))
      (node (ref "Q23") (pin "G") (pinfunction "G_G") (pintype "passive"))
      (node (ref "R49") (pin "1") (pinfunction "1_1") (pintype "passive"))
      (node (ref "R50") (pin "2") (pinfunction "2_2") (pintype "passive"))
    )
    (net (code "121") (name "Net-(Q22-PadS)") (class "Default")
      (node (ref "Q22") (pin "S") (pinfunction "S_S") (pintype "passive"))
      (node (ref "Q23") (pin "S") (pinfunction "S_S") (pintype "passive"))
      (node (ref "R49") (pin "2") (pinfunction "2_2") (pintype "passive"))
    )
    (net (code "122") (name "Net-(Q24-PadG)") (class "Default")
      (node (ref "Q24") (pin "G") (pinfunction "G_G") (pintype "passive"))
      (node (ref "Q25") (pin "G") (pinfunction "G_G") (pintype "passive"))
      (node (ref "R51") (pin "1") (pinfunction "1_1") (pintype "passive"))
      (node (ref "R52") (pin "2") (pinfunction "2_2") (pintype "passive"))
    )
    (net (code "123") (name "Net-(Q24-PadS)") (class "Default")
      (node (ref "Q24") (pin "S") (pinfunction "S_S") (pintype "passive"))
      (node (ref "Q25") (pin "S") (pinfunction "S_S") (pintype "passive"))
      (node (ref "R51") (pin "2") (pinfunction "2_2") (pintype "passive"))
    )
    (net (code "124") (name "Net-(Q26-PadG)") (class "Default")
      (node (ref "Q26") (pin "G") (pinfunction "G_G") (pintype "passive"))
      (node (ref "Q27") (pin "G") (pinfunction "G_G") (pintype "passive"))
      (node (ref "R57") (pin "1") (pinfunction "1_1") (pintype "passive"))
      (node (ref "R58") (pin "2") (pinfunction "2_2") (pintype "passive"))
    )
    (net (code "125") (name "Net-(Q26-PadS)") (class "Default")
      (node (ref "Q26") (pin "S") (pinfunction "S_S") (pintype "passive"))
      (node (ref "Q27") (pin "S") (pinfunction "S_S") (pintype "passive"))
      (node (ref "R57") (pin "2") (pinfunction "2_2") (pintype "passive"))
    )
    (net (code "126") (name "Net-(Q28-PadG)") (class "Default")
      (node (ref "Q28") (pin "G") (pinfunction "G_G") (pintype "passive"))
      (node (ref "Q29") (pin "G") (pinfunction "G_G") (pintype "passive"))
      (node (ref "R59") (pin "1") (pinfunction "1_1") (pintype "passive"))
      (node (ref "R60") (pin "2") (pinfunction "2_2") (pintype "passive"))
    )
    (net (code "127") (name "Net-(Q28-PadS)") (class "Default")
      (node (ref "Q28") (pin "S") (pinfunction "S_S") (pintype "passive"))
      (node (ref "Q29") (pin "S") (pinfunction "S_S") (pintype "passive"))
      (node (ref "R59") (pin "2") (pinfunction "2_2") (pintype "passive"))
    )
    (net (code "128") (name "Net-(Q31-PadG)") (class "Default")
      (node (ref "Q31") (pin "G") (pinfunction "G_G") (pintype "passive"))
      (node (ref "Q32") (pin "G") (pinfunction "G_G") (pintype "passive"))
      (node (ref "R63") (pin "1") (pinfunction "1_1") (pintype "passive"))
      (node (ref "R64") (pin "2") (pinfunction "2_2") (pintype "passive"))
    )
    (net (code "129") (name "Net-(Q31-PadS)") (class "Default")
      (node (ref "Q31") (pin "S") (pinfunction "S_S") (pintype "passive"))
      (node (ref "Q32") (pin "S") (pinfunction "S_S") (pintype "passive"))
      (node (ref "R63") (pin "2") (pinfunction "2_2") (pintype "passive"))
    )
    (net (code "130") (name "Net-(Q33-PadG)") (class "Default")
      (node (ref "Q33") (pin "G") (pinfunction "G_G") (pintype "passive"))
      (node (ref "Q38") (pin "G") (pinfunction "G_G") (pintype "passive"))
      (node (ref "R73") (pin "1") (pinfunction "1_1") (pintype "passive"))
      (node (ref "R74") (pin "2") (pinfunction "2_2") (pintype "passive"))
    )
    (net (code "131") (name "Net-(Q33-PadS)") (class "Default")
      (node (ref "Q33") (pin "S") (pinfunction "S_S") (pintype "passive"))
      (node (ref "Q38") (pin "S") (pinfunction "S_S") (pintype "passive"))
      (node (ref "R73") (pin "2") (pinfunction "2_2") (pintype "passive"))
    )
    (net (code "132") (name "Net-(Q34-PadG)") (class "Default")
      (node (ref "Q34") (pin "G") (pinfunction "G_G") (pintype "passive"))
      (node (ref "Q35") (pin "G") (pinfunction "G_G") (pintype "passive"))
      (node (ref "R71") (pin "1") (pinfunction "1_1") (pintype "passive"))
      (node (ref "R72") (pin "2") (pinfunction "2_2") (pintype "passive"))
    )
    (net (code "133") (name "Net-(Q34-PadS)") (class "Default")
      (node (ref "Q34") (pin "S") (pinfunction "S_S") (pintype "passive"))
      (node (ref "Q35") (pin "S") (pinfunction "S_S") (pintype "passive"))
      (node (ref "R71") (pin "2") (pinfunction "2_2") (pintype "passive"))
    )
    (net (code "134") (name "Net-(Q36-PadG)") (class "Default")
      (node (ref "Q36") (pin "G") (pinfunction "G_G") (pintype "passive"))
      (node (ref "Q37") (pin "G") (pinfunction "G_G") (pintype "passive"))
      (node (ref "R69") (pin "1") (pinfunction "1_1") (pintype "passive"))
      (node (ref "R70") (pin "2") (pinfunction "2_2") (pintype "passive"))
    )
    (net (code "135") (name "Net-(Q36-PadS)") (class "Default")
      (node (ref "Q36") (pin "S") (pinfunction "S_S") (pintype "passive"))
      (node (ref "Q37") (pin "S") (pinfunction "S_S") (pintype "passive"))
      (node (ref "R69") (pin "2") (pinfunction "2_2") (pintype "passive"))
    )
    (net (code "136") (name "Net-(Q39-PadG)") (class "Default")
      (node (ref "Q39") (pin "G") (pinfunction "G_G") (pintype "passive"))
      (node (ref "Q40") (pin "G") (pinfunction "G_G") (pintype "passive"))
      (node (ref "R75") (pin "1") (pinfunction "1_1") (pintype "passive"))
      (node (ref "R76") (pin "2") (pinfunction "2_2") (pintype "passive"))
    )
    (net (code "137") (name "Net-(Q39-PadS)") (class "Default")
      (node (ref "Q39") (pin "S") (pinfunction "S_S") (pintype "passive"))
      (node (ref "Q40") (pin "S") (pinfunction "S_S") (pintype "passive"))
      (node (ref "R75") (pin "2") (pinfunction "2_2") (pintype "passive"))
    )
    (net (code "138") (name "Net-(Q41-PadG)") (class "Default")
      (node (ref "Q41") (pin "G") (pinfunction "G_G") (pintype "passive"))
      (node (ref "Q42") (pin "G") (pinfunction "G_G") (pintype "passive"))
      (node (ref "R85") (pin "1") (pinfunction "1_1") (pintype "passive"))
      (node (ref "R86") (pin "2") (pinfunction "2_2") (pintype "passive"))
    )
    (net (code "139") (name "Net-(Q41-PadS)") (class "Default")
      (node (ref "Q41") (pin "S") (pinfunction "S_S") (pintype "passive"))
      (node (ref "Q42") (pin "S") (pinfunction "S_S") (pintype "passive"))
      (node (ref "R85") (pin "2") (pinfunction "2_2") (pintype "passive"))
    )
    (net (code "140") (name "Net-(Q43-PadG)") (class "Default")
      (node (ref "Q43") (pin "G") (pinfunction "G_G") (pintype "passive"))
      (node (ref "Q44") (pin "G") (pinfunction "G_G") (pintype "passive"))
      (node (ref "R87") (pin "1") (pinfunction "1_1") (pintype "passive"))
      (node (ref "R88") (pin "2") (pinfunction "2_2") (pintype "passive"))
    )
    (net (code "141") (name "Net-(Q43-PadS)") (class "Default")
      (node (ref "Q43") (pin "S") (pinfunction "S_S") (pintype "passive"))
      (node (ref "Q44") (pin "S") (pinfunction "S_S") (pintype "passive"))
      (node (ref "R87") (pin "2") (pinfunction "2_2") (pintype "passive"))
    )
    (net (code "142") (name "Net-(Q45-PadG)") (class "Default")
      (node (ref "Q45") (pin "G") (pinfunction "G_G") (pintype "passive"))
      (node (ref "Q46") (pin "G") (pinfunction "G_G") (pintype "passive"))
      (node (ref "R83") (pin "1") (pinfunction "1_1") (pintype "passive"))
      (node (ref "R84") (pin "2") (pinfunction "2_2") (pintype "passive"))
    )
    (net (code "143") (name "Net-(Q45-PadS)") (class "Default")
      (node (ref "Q45") (pin "S") (pinfunction "S_S") (pintype "passive"))
      (node (ref "Q46") (pin "S") (pinfunction "S_S") (pintype "passive"))
      (node (ref "R83") (pin "2") (pinfunction "2_2") (pintype "passive"))
    )
    (net (code "144") (name "Net-(Q47-PadG)") (class "Default")
      (node (ref "Q47") (pin "G") (pinfunction "G_G") (pintype "passive"))
      (node (ref "Q48") (pin "G") (pinfunction "G_G") (pintype "passive"))
      (node (ref "R81") (pin "1") (pinfunction "1_1") (pintype "passive"))
      (node (ref "R82") (pin "2") (pinfunction "2_2") (pintype "passive"))
    )
    (net (code "145") (name "Net-(Q47-PadS)") (class "Default")
      (node (ref "Q47") (pin "S") (pinfunction "S_S") (pintype "passive"))
      (node (ref "Q48") (pin "S") (pinfunction "S_S") (pintype "passive"))
      (node (ref "R81") (pin "2") (pinfunction "2_2") (pintype "passive"))
    )
    (net (code "146") (name "Net-(Q49-PadG)") (class "Default")
      (node (ref "Q49") (pin "G") (pinfunction "G_G") (pintype "passive"))
      (node (ref "Q53") (pin "G") (pinfunction "G_G") (pintype "passive"))
      (node (ref "R94") (pin "1") (pinfunction "1_1") (pintype "passive"))
      (node (ref "R95") (pin "2") (pinfunction "2_2") (pintype "passive"))
    )
    (net (code "147") (name "Net-(Q50-PadG)") (class "Default")
      (node (ref "Q50") (pin "G") (pinfunction "G_G") (pintype "passive"))
      (node (ref "Q54") (pin "G") (pinfunction "G_G") (pintype "passive"))
      (node (ref "R104") (pin "1") (pinfunction "1_1") (pintype "passive"))
      (node (ref "R105") (pin "2") (pinfunction "2_2") (pintype "passive"))
    )
    (net (code "148") (name "Net-(Q51-PadG)") (class "Default")
      (node (ref "Q51") (pin "G") (pinfunction "G_G") (pintype "passive"))
      (node (ref "Q55") (pin "G") (pinfunction "G_G") (pintype "passive"))
      (node (ref "R109") (pin "1") (pinfunction "1_1") (pintype "passive"))
      (node (ref "R110") (pin "2") (pinfunction "2_2") (pintype "passive"))
    )
    (net (code "149") (name "Net-(Q52-PadG)") (class "Default")
      (node (ref "Q52") (pin "G") (pinfunction "G_G") (pintype "passive"))
      (node (ref "Q56") (pin "G") (pinfunction "G_G") (pintype "passive"))
      (node (ref "R100") (pin "2") (pinfunction "2_2") (pintype "passive"))
      (node (ref "R99") (pin "1") (pinfunction "1_1") (pintype "passive"))
    )
    (net (code "150") (name "Net-(U1-BAT)") (class "Default")
      (node (ref "R37") (pin "2") (pinfunction "2_2") (pintype "passive"))
      (node (ref "U1") (pin "10") (pinfunction "BAT_10") (pintype "passive"))
    )
    (net (code "151") (name "Net-(U1-CAP1)") (class "Default")
      (node (ref "C25") (pin "1") (pinfunction "1_1") (pintype "passive"))
      (node (ref "U1") (pin "7") (pinfunction "CAP1_7") (pintype "output"))
    )
    (net (code "152") (name "OIN1+") (class "Default")
      (node (ref "IC19") (pin "3") (pinfunction "E_3") (pintype "bidirectional"))
      (node (ref "R84") (pin "1") (pinfunction "1_1") (pintype "passive"))
    )
    (net (code "153") (name "OIN1-") (class "Default")
      (node (ref "IC20") (pin "3") (pinfunction "E_3") (pintype "bidirectional"))
      (node (ref "R86") (pin "1") (pinfunction "1_1") (pintype "passive"))
    )
    (net (code "154") (name "OIN2+") (class "Default")
      (node (ref "IC15") (pin "3") (pinfunction "E_3") (pintype "bidirectional"))
      (node (ref "R72") (pin "1") (pinfunction "1_1") (pintype "passive"))
    )
    (net (code "155") (name "OIN2-") (class "Default")
      (node (ref "IC16") (pin "3") (pinfunction "E_3") (pintype "bidirectional"))
      (node (ref "R74") (pin "1") (pinfunction "1_1") (pintype "passive"))
    )
    (net (code "156") (name "OIN3+") (class "Default")
      (node (ref "IC11") (pin "4") (pinfunction "C_4") (pintype "bidirectional"))
      (node (ref "R60") (pin "1") (pinfunction "1_1") (pintype "passive"))
    )
    (net (code "157") (name "OIN3-") (class "Default")
      (node (ref "IC12") (pin "3") (pinfunction "E_3") (pintype "bidirectional"))
      (node (ref "R62") (pin "1") (pinfunction "1_1") (pintype "passive"))
    )
    (net (code "158") (name "OIN4+") (class "Default")
      (node (ref "IC7") (pin "4") (pinfunction "C_4") (pintype "bidirectional"))
      (node (ref "R48") (pin "1") (pinfunction "1_1") (pintype "passive"))
    )
    (net (code "159") (name "OIN4-") (class "Default")
      (node (ref "IC8") (pin "4") (pinfunction "C_4") (pintype "bidirectional"))
      (node (ref "R50") (pin "1") (pinfunction "1_1") (pintype "passive"))
    )
    (net (code "160") (name "OIN5+") (class "Default")
      (node (ref "IC3") (pin "4") (pinfunction "C_4") (pintype "bidirectional"))
      (node (ref "R5") (pin "1") (pinfunction "1_1") (pintype "passive"))
    )
    (net (code "161") (name "OIN5-") (class "Default")
      (node (ref "IC4") (pin "4") (pinfunction "C_4") (pintype "bidirectional"))
      (node (ref "R7") (pin "1") (pinfunction "1_1") (pintype "passive"))
    )
    (net (code "162") (name "OOUT1+") (class "Default")
      (node (ref "IC17") (pin "3") (pinfunction "E_3") (pintype "bidirectional"))
      (node (ref "R82") (pin "1") (pinfunction "1_1") (pintype "passive"))
    )
    (net (code "163") (name "OOUT1-") (class "Default")
      (node (ref "IC18") (pin "3") (pinfunction "E_3") (pintype "bidirectional"))
      (node (ref "R88") (pin "1") (pinfunction "1_1") (pintype "passive"))
    )
    (net (code "164") (name "OOUT2+") (class "Default")
      (node (ref "IC13") (pin "3") (pinfunction "E_3") (pintype "bidirectional"))
      (node (ref "R70") (pin "1") (pinfunction "1_1") (pintype "passive"))
    )
    (net (code "165") (name "OOUT2-") (class "Default")
      (node (ref "IC14") (pin "3") (pinfunction "E_3") (pintype "bidirectional"))
      (node (ref "R76") (pin "1") (pinfunction "1_1") (pintype "passive"))
    )
    (net (code "166") (name "OOUT3+") (class "Default")
      (node (ref "IC9") (pin "4") (pinfunction "C_4") (pintype "bidirectional"))
      (node (ref "R58") (pin "1") (pinfunction "1_1") (pintype "passive"))
    )
    (net (code "167") (name "OOUT3-") (class "Default")
      (node (ref "IC10") (pin "3") (pinfunction "E_3") (pintype "bidirectional"))
      (node (ref "R64") (pin "1") (pinfunction "1_1") (pintype "passive"))
    )
    (net (code "168") (name "OOUT4+") (class "Default")
      (node (ref "IC5") (pin "4") (pinfunction "C_4") (pintype "bidirectional"))
      (node (ref "R46") (pin "1") (pinfunction "1_1") (pintype "passive"))
    )
    (net (code "169") (name "OOUT4-") (class "Default")
      (node (ref "IC6") (pin "4") (pinfunction "C_4") (pintype "bidirectional"))
      (node (ref "R52") (pin "1") (pinfunction "1_1") (pintype "passive"))
    )
    (net (code "170") (name "OOUT5+") (class "Default")
      (node (ref "IC1") (pin "4") (pinfunction "C_4") (pintype "bidirectional"))
      (node (ref "R3") (pin "1") (pinfunction "1_1") (pintype "passive"))
    )
    (net (code "171") (name "OOUT5-") (class "Default")
      (node (ref "IC2") (pin "4") (pinfunction "C_4") (pintype "bidirectional"))
      (node (ref "R40") (pin "1") (pinfunction "1_1") (pintype "passive"))
    )
    (net (code "172") (name "OUT+") (class "Default")
      (node (ref "C56") (pin "1") (pinfunction "1_1") (pintype "passive"))
      (node (ref "D20") (pin "1") (pinfunction "K_1") (pintype "bidirectional"))
      (node (ref "JP142") (pin "P$1") (pinfunction "1_P$1") (pintype "passive"))
      (node (ref "Q18") (pin "D") (pinfunction "D_D") (pintype "passive"))
      (node (ref "Q26") (pin "D") (pinfunction "D_D") (pintype "passive"))
      (node (ref "Q36") (pin "D") (pinfunction "D_D") (pintype "passive"))
      (node (ref "Q47") (pin "D") (pinfunction "D_D") (pintype "passive"))
      (node (ref "Q50") (pin "D") (pinfunction "D_D") (pintype "passive"))
      (node (ref "Q7") (pin "D") (pinfunction "D_D") (pintype "passive"))
    )
    (net (code "173") (name "OUT-") (class "Default")
      (node (ref "C62") (pin "1") (pinfunction "1_1") (pintype "passive"))
      (node (ref "D22") (pin "1") (pinfunction "K_1") (pintype "bidirectional"))
      (node (ref "Q17") (pin "D") (pinfunction "D_D") (pintype "passive"))
      (node (ref "Q25") (pin "D") (pinfunction "D_D") (pintype "passive"))
      (node (ref "Q32") (pin "D") (pinfunction "D_D") (pintype "passive"))
      (node (ref "Q40") (pin "D") (pinfunction "D_D") (pintype "passive"))
      (node (ref "Q44") (pin "D") (pinfunction "D_D") (pintype "passive"))
      (node (ref "Q51") (pin "D") (pinfunction "D_D") (pintype "passive"))
    )
    (net (code "174") (name "PACK-") (class "Default")
      (node (ref "CON2") (pin "-") (pinfunction "-_-") (pintype "power_in"))
      (node (ref "Q10") (pin "3") (pinfunction "S_3") (pintype "passive"))
      (node (ref "R35") (pin "2") (pinfunction "2_2") (pintype "passive"))
    )
    (net (code "175") (name "RXD") (class "Default")
      (node (ref "JP110") (pin "1") (pinfunction "1_1") (pintype "passive"))
      (node (ref "JP72") (pin "1") (pinfunction "1_1") (pintype "passive"))
      (node (ref "JP91") (pin "1") (pinfunction "1_1") (pintype "passive"))
    )
    (net (code "176") (name "SCL") (class "Default")
      (node (ref "JP112") (pin "1") (pinfunction "1_1") (pintype "passive"))
      (node (ref "JP74") (pin "1") (pinfunction "1_1") (pintype "passive"))
      (node (ref "JP93") (pin "1") (pinfunction "1_1") (pintype "passive"))
      (node (ref "R9") (pin "2") (pinfunction "2_2") (pintype "passive"))
      (node (ref "U1") (pin "5") (pinfunction "SCL_5") (pintype "input"))
    )
    (net (code "177") (name "SD0") (class "Default")
      (node (ref "JP59") (pin "1") (pinfunction "1_1") (pintype "passive"))
      (node (ref "JP78") (pin "1") (pinfunction "1_1") (pintype "passive"))
      (node (ref "JP97") (pin "1") (pinfunction "1_1") (pintype "passive"))
    )
    (net (code "178") (name "SD1") (class "Default")
      (node (ref "JP60") (pin "1") (pinfunction "1_1") (pintype "passive"))
      (node (ref "JP79") (pin "1") (pinfunction "1_1") (pintype "passive"))
      (node (ref "JP98") (pin "1") (pinfunction "1_1") (pintype "passive"))
    )
    (net (code "179") (name "SD2") (class "Default")
      (node (ref "JP16") (pin "1") (pinfunction "1_1") (pintype "passive"))
      (node (ref "JP35") (pin "1") (pinfunction "1_1") (pintype "passive"))
      (node (ref "JP54") (pin "1") (pinfunction "1_1") (pintype "passive"))
    )
    (net (code "180") (name "SD3") (class "Default")
      (node (ref "JP17") (pin "1") (pinfunction "1_1") (pintype "passive"))
      (node (ref "JP36") (pin "1") (pinfunction "1_1") (pintype "passive"))
      (node (ref "JP55") (pin "1") (pinfunction "1_1") (pintype "passive"))
    )
    (net (code "181") (name "SDA") (class "Default")
      (node (ref "JP109") (pin "1") (pinfunction "1_1") (pintype "passive"))
      (node (ref "JP71") (pin "1") (pinfunction "1_1") (pintype "passive"))
      (node (ref "JP90") (pin "1") (pinfunction "1_1") (pintype "passive"))
      (node (ref "R8") (pin "2") (pinfunction "2_2") (pintype "passive"))
      (node (ref "U1") (pin "4") (pinfunction "SDA_4") (pintype "bidirectional"))
    )
    (net (code "182") (name "SN") (class "Default")
      (node (ref "JP23") (pin "1") (pinfunction "1_1") (pintype "passive"))
      (node (ref "JP4") (pin "1") (pinfunction "1_1") (pintype "passive"))
      (node (ref "JP42") (pin "1") (pinfunction "1_1") (pintype "passive"))
    )
    (net (code "183") (name "SNS3.3V") (class "Default")
      (node (ref "C28") (pin "1") (pinfunction "1_1") (pintype "passive"))
      (node (ref "C29") (pin "1") (pinfunction "1_1") (pintype "passive"))
      (node (ref "C8") (pin "1") (pinfunction "1_1") (pintype "passive"))
      (node (ref "IC25") (pin "8") (pinfunction "VS_8") (pintype "bidirectional"))
      (node (ref "IC26") (pin "8") (pinfunction "VS_8") (pintype "bidirectional"))
      (node (ref "IC27") (pin "2") (pinfunction "VOUT_1_2") (pintype "bidirectional"))
      (node (ref "IC27") (pin "4") (pinfunction "VOUT_2_4") (pintype "bidirectional"))
      (node (ref "JP126") (pin "1") (pinfunction "1_1") (pintype "passive"))
      (node (ref "JP128") (pin "1") (pinfunction "1_1") (pintype "passive"))
    )
    (net (code "184") (name "SNSIN") (class "Default")
      (node (ref "C6") (pin "1") (pinfunction "1_1") (pintype "passive"))
      (node (ref "D1") (pin "1") (pinfunction "K_1") (pintype "bidirectional"))
      (node (ref "IC25") (pin "1") (pinfunction "IN+_1_1") (pintype "bidirectional"))
      (node (ref "IC25") (pin "2") (pinfunction "IN+_2_2") (pintype "bidirectional"))
      (node (ref "JP137") (pin "P$1") (pinfunction "1_P$1") (pintype "passive"))
      (node (ref "Q53") (pin "D") (pinfunction "D_D") (pintype "passive"))
    )
    (net (code "185") (name "SNSOUT") (class "Default")
      (node (ref "C55") (pin "1") (pinfunction "1_1") (pintype "passive"))
      (node (ref "D19") (pin "1") (pinfunction "K_1") (pintype "bidirectional"))
      (node (ref "IC26") (pin "3") (pinfunction "IN-_1_3") (pintype "bidirectional"))
      (node (ref "IC26") (pin "4") (pinfunction "IN-_2_4") (pintype "bidirectional"))
      (node (ref "JP140") (pin "P$1") (pinfunction "1_P$1") (pintype "passive"))
      (node (ref "Q54") (pin "D") (pinfunction "D_D") (pintype "passive"))
    )
    (net (code "186") (name "SP") (class "Default")
      (node (ref "JP22") (pin "1") (pinfunction "1_1") (pintype "passive"))
      (node (ref "JP3") (pin "1") (pinfunction "1_1") (pintype "passive"))
      (node (ref "JP41") (pin "1") (pinfunction "1_1") (pintype "passive"))
    )
    (net (code "187") (name "SRN") (class "Default")
      (node (ref "C20") (pin "2") (pinfunction "2_2") (pintype "passive"))
      (node (ref "C21") (pin "1") (pinfunction "1_1") (pintype "passive"))
      (node (ref "R33") (pin "2") (pinfunction "2_2") (pintype "passive"))
      (node (ref "U1") (pin "19") (pinfunction "SRN_19") (pintype "input"))
    )
    (net (code "188") (name "SRP") (class "Default")
      (node (ref "C19") (pin "2") (pinfunction "2_2") (pintype "passive"))
      (node (ref "C20") (pin "1") (pinfunction "1_1") (pintype "passive"))
      (node (ref "R31") (pin "2") (pinfunction "2_2") (pintype "passive"))
      (node (ref "U1") (pin "18") (pinfunction "SRP_18") (pintype "input"))
    )
    (net (code "189") (name "TXD") (class "Default")
      (node (ref "JP111") (pin "1") (pinfunction "1_1") (pintype "passive"))
      (node (ref "JP73") (pin "1") (pinfunction "1_1") (pintype "passive"))
      (node (ref "JP92") (pin "1") (pinfunction "1_1") (pintype "passive"))
    )
    (net (code "190") (name "VC0") (class "Default")
      (node (ref "C18") (pin "2") (pinfunction "2_2") (pintype "passive"))
      (node (ref "R15") (pin "2") (pinfunction "2_2") (pintype "passive"))
      (node (ref "U1") (pin "17") (pinfunction "VC0_17") (pintype "input"))
    )
    (net (code "191") (name "VC1") (class "Default")
      (node (ref "C16") (pin "2") (pinfunction "2_2") (pintype "passive"))
      (node (ref "C17") (pin "1") (pinfunction "1_1") (pintype "passive"))
      (node (ref "R14") (pin "2") (pinfunction "2_2") (pintype "passive"))
      (node (ref "R27") (pin "2") (pinfunction "2_2") (pintype "passive"))
      (node (ref "S2") (pin "1") (pinfunction "1_1") (pintype "passive"))
      (node (ref "S2") (pin "2") (pinfunction "1_2") (pintype "passive"))
      (node (ref "U1") (pin "16") (pinfunction "VC1_16") (pintype "input"))
    )
    (net (code "192") (name "VC2") (class "Default")
      (node (ref "C15") (pin "2") (pinfunction "2_2") (pintype "passive"))
      (node (ref "C16") (pin "1") (pinfunction "1_1") (pintype "passive"))
      (node (ref "R13") (pin "2") (pinfunction "2_2") (pintype "passive"))
      (node (ref "R24") (pin "2") (pinfunction "2_2") (pintype "passive"))
      (node (ref "U1") (pin "15") (pinfunction "VC2_15") (pintype "input"))
    )
    (net (code "193") (name "VC3") (class "Default")
      (node (ref "C14") (pin "2") (pinfunction "2_2") (pintype "passive"))
      (node (ref "C15") (pin "1") (pinfunction "1_1") (pintype "passive"))
      (node (ref "R12") (pin "2") (pinfunction "2_2") (pintype "passive"))
      (node (ref "R21") (pin "2") (pinfunction "2_2") (pintype "passive"))
      (node (ref "U1") (pin "14") (pinfunction "VC3_14") (pintype "input"))
    )
    (net (code "194") (name "VC4") (class "Default")
      (node (ref "C13") (pin "2") (pinfunction "2_2") (pintype "passive"))
      (node (ref "C14") (pin "1") (pinfunction "1_1") (pintype "passive"))
      (node (ref "R11") (pin "2") (pinfunction "2_2") (pintype "passive"))
      (node (ref "R18") (pin "2") (pinfunction "2_2") (pintype "passive"))
      (node (ref "U1") (pin "13") (pinfunction "VC4_13") (pintype "input"))
    )
    (net (code "195") (name "VC5") (class "Default")
      (node (ref "C13") (pin "1") (pinfunction "1_1") (pintype "passive"))
      (node (ref "R10") (pin "2") (pinfunction "2_2") (pintype "passive"))
      (node (ref "U1") (pin "12") (pinfunction "VC5_12") (pintype "input"))
    )
    (net (code "196") (name "unconnected-(IC21-N.C._1-Pad1)") (class "Default")
      (node (ref "IC21") (pin "1") (pinfunction "N.C._1_1") (pintype "bidirectional"))
    )
    (net (code "197") (name "unconnected-(IC21-N.C._2-Pad4)") (class "Default")
      (node (ref "IC21") (pin "4") (pinfunction "N.C._2_4") (pintype "bidirectional"))
    )
    (net (code "198") (name "unconnected-(IC21-N.C._3-Pad7)") (class "Default")
      (node (ref "IC21") (pin "7") (pinfunction "N.C._3_7") (pintype "bidirectional"))
    )
    (net (code "199") (name "unconnected-(IC22-N.C._1-Pad1)") (class "Default")
      (node (ref "IC22") (pin "1") (pinfunction "N.C._1_1") (pintype "bidirectional"))
    )
    (net (code "200") (name "unconnected-(IC22-N.C._2-Pad4)") (class "Default")
      (node (ref "IC22") (pin "4") (pinfunction "N.C._2_4") (pintype "bidirectional"))
    )
    (net (code "201") (name "unconnected-(IC22-N.C._3-Pad7)") (class "Default")
      (node (ref "IC22") (pin "7") (pinfunction "N.C._3_7") (pintype "bidirectional"))
    )
    (net (code "202") (name "unconnected-(IC23-N.C._1-Pad1)") (class "Default")
      (node (ref "IC23") (pin "1") (pinfunction "N.C._1_1") (pintype "bidirectional"))
    )
    (net (code "203") (name "unconnected-(IC23-N.C._2-Pad4)") (class "Default")
      (node (ref "IC23") (pin "4") (pinfunction "N.C._2_4") (pintype "bidirectional"))
    )
    (net (code "204") (name "unconnected-(IC23-N.C._3-Pad7)") (class "Default")
      (node (ref "IC23") (pin "7") (pinfunction "N.C._3_7") (pintype "bidirectional"))
    )
    (net (code "205") (name "unconnected-(IC24-N.C._1-Pad1)") (class "Default")
      (node (ref "IC24") (pin "1") (pinfunction "N.C._1_1") (pintype "bidirectional"))
    )
    (net (code "206") (name "unconnected-(IC24-N.C._2-Pad4)") (class "Default")
      (node (ref "IC24") (pin "4") (pinfunction "N.C._2_4") (pintype "bidirectional"))
    )
    (net (code "207") (name "unconnected-(IC24-N.C._3-Pad7)") (class "Default")
      (node (ref "IC24") (pin "7") (pinfunction "N.C._3_7") (pintype "bidirectional"))
    )
    (net (code "208") (name "unconnected-(IC25-NC-Pad6)") (class "Default")
      (node (ref "IC25") (pin "6") (pinfunction "NC_6") (pintype "no_connect"))
    )
    (net (code "209") (name "unconnected-(IC26-NC-Pad6)") (class "Default")
      (node (ref "IC26") (pin "6") (pinfunction "NC_6") (pintype "no_connect"))
    )
    (net (code "210") (name "unconnected-(U1-NC-Pad11)") (class "Default")
      (node (ref "U1") (pin "11") (pinfunction "NC_11") (pintype "no_connect"))
    )
  )
)
